# Prop_Fan.net
KiCad netlist of a schematic drawn in EAGLE
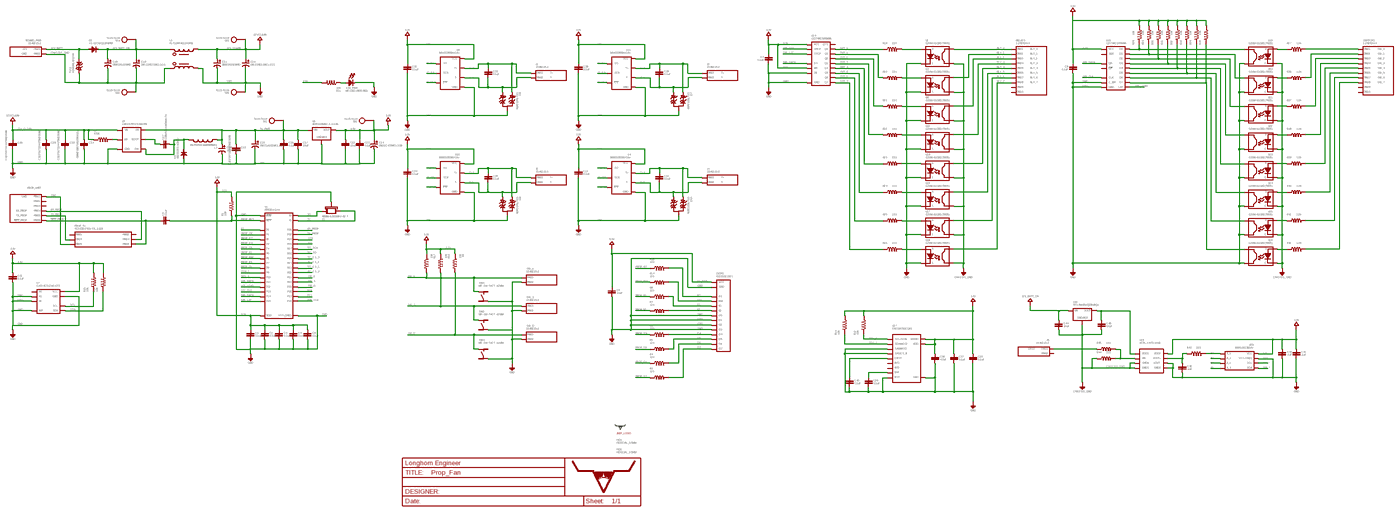
[diagram p0: schematic, sheet 1, overview]
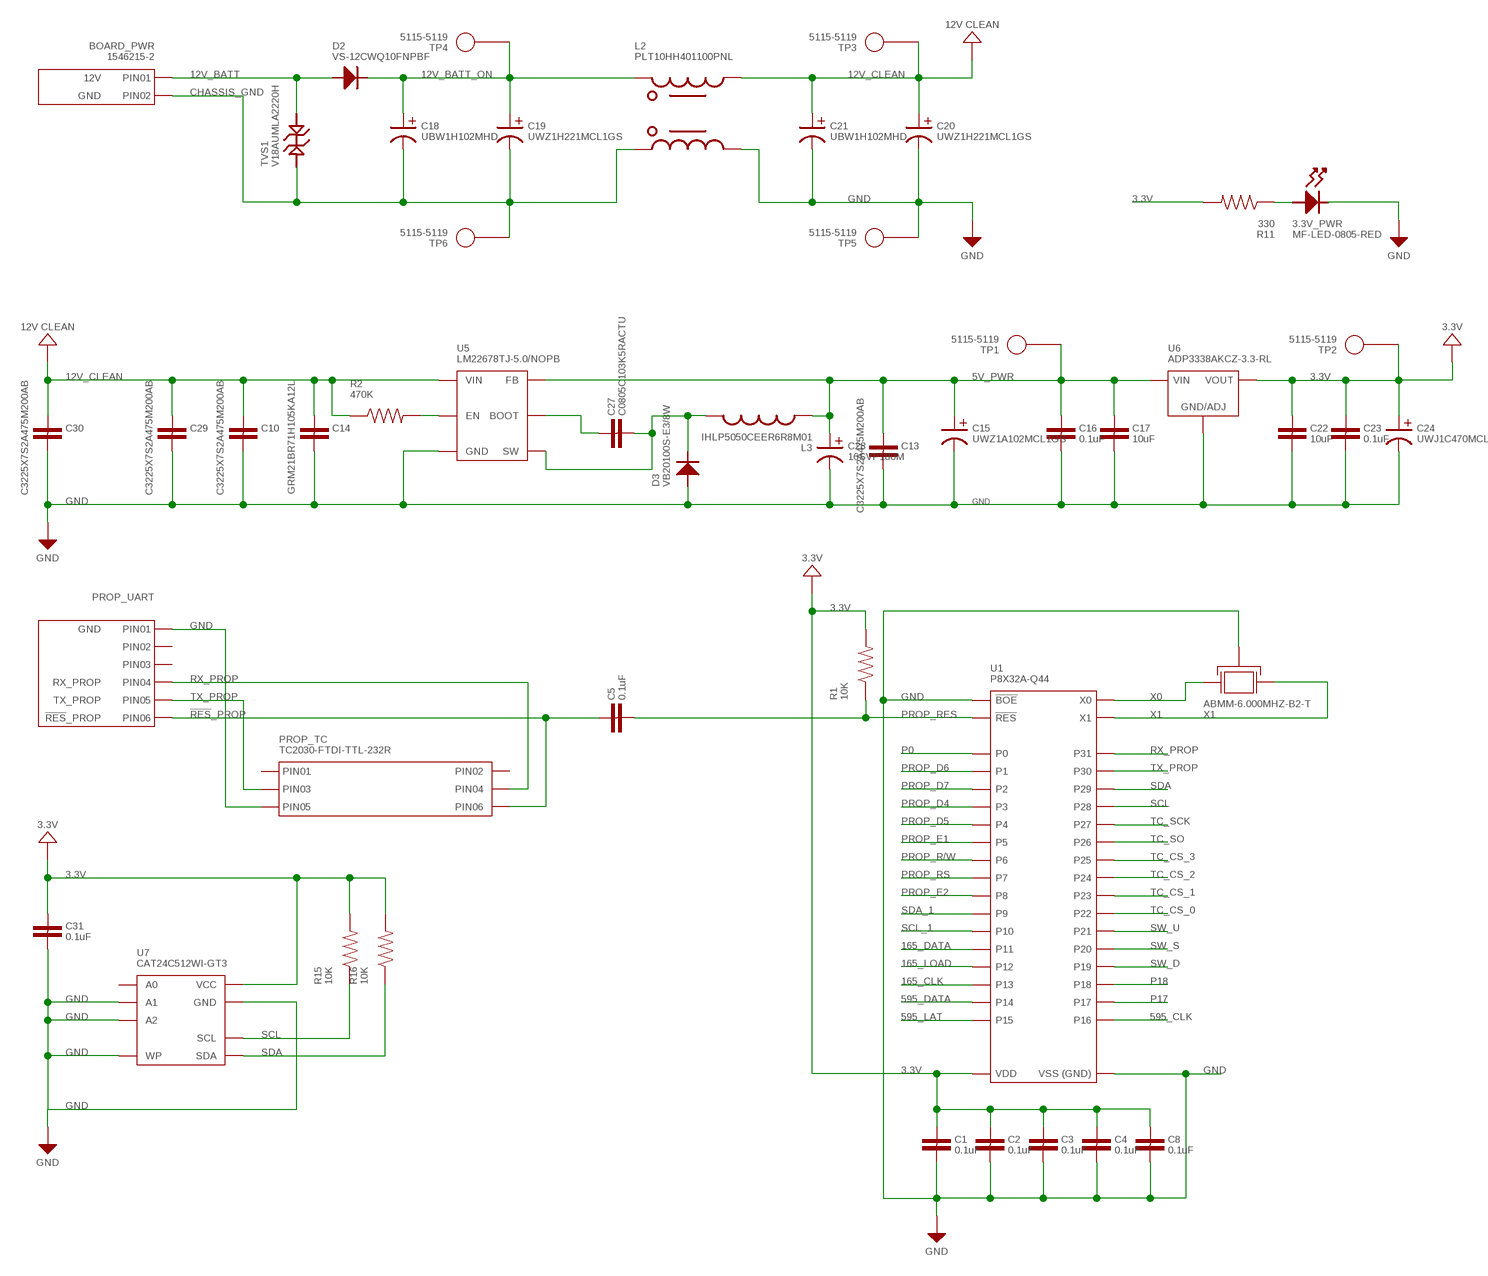
[diagram p1: schematic, sheet 1, part 1 of 4]
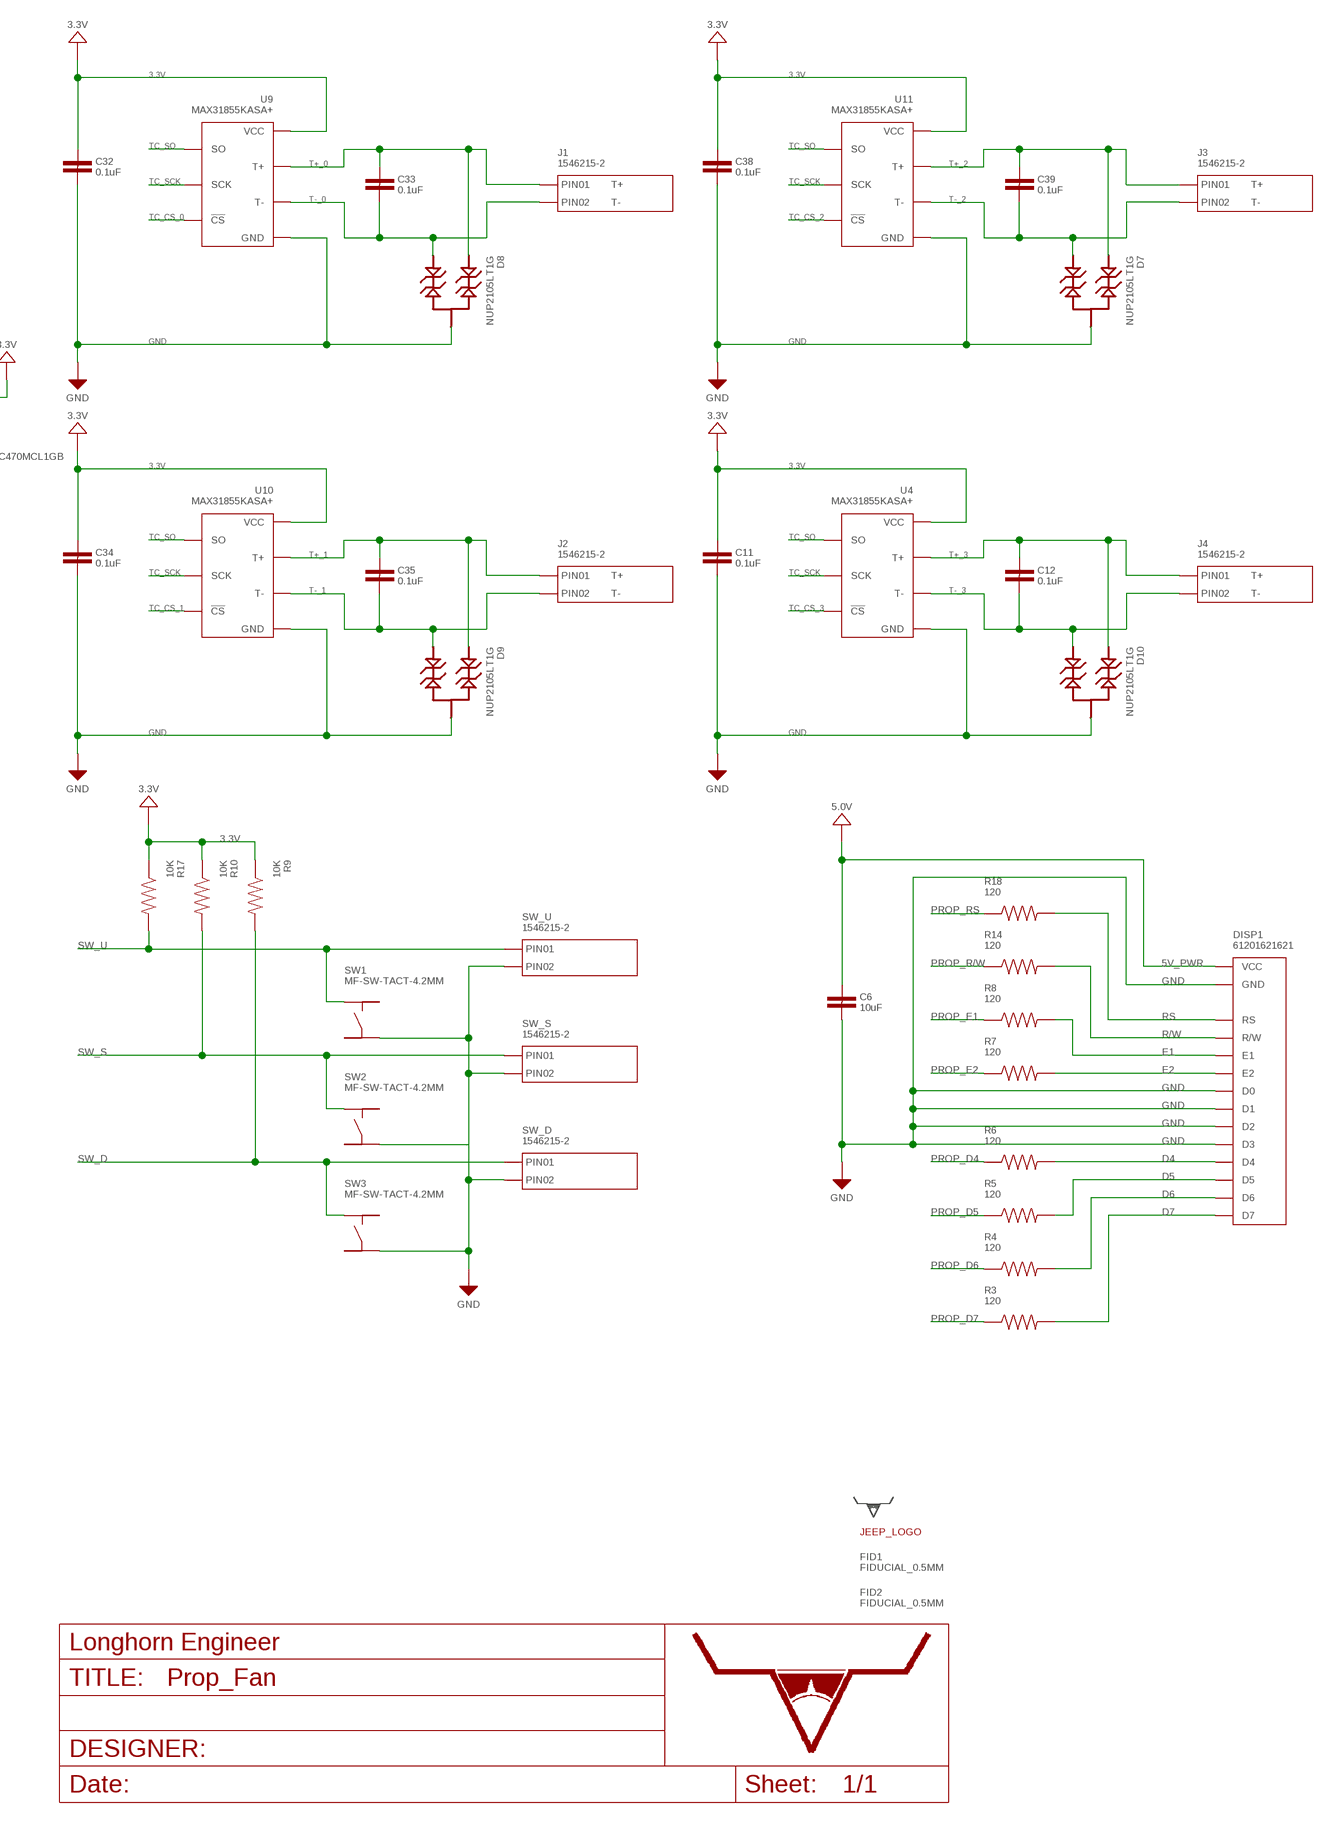
[diagram p2: schematic, sheet 1, part 2 of 4]
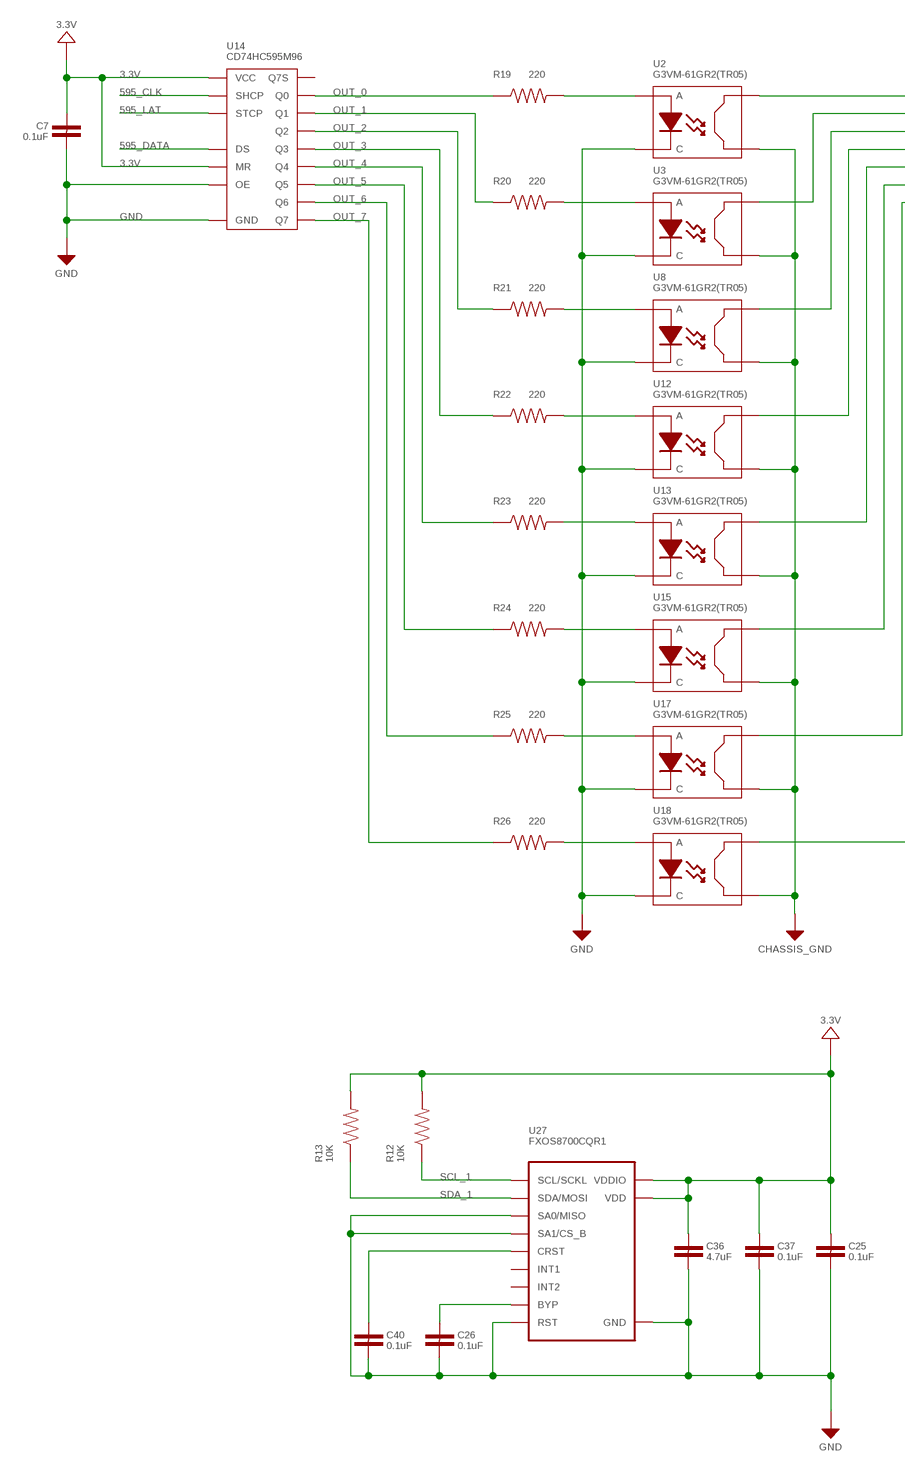
[diagram p3: schematic, sheet 1, part 3 of 4]
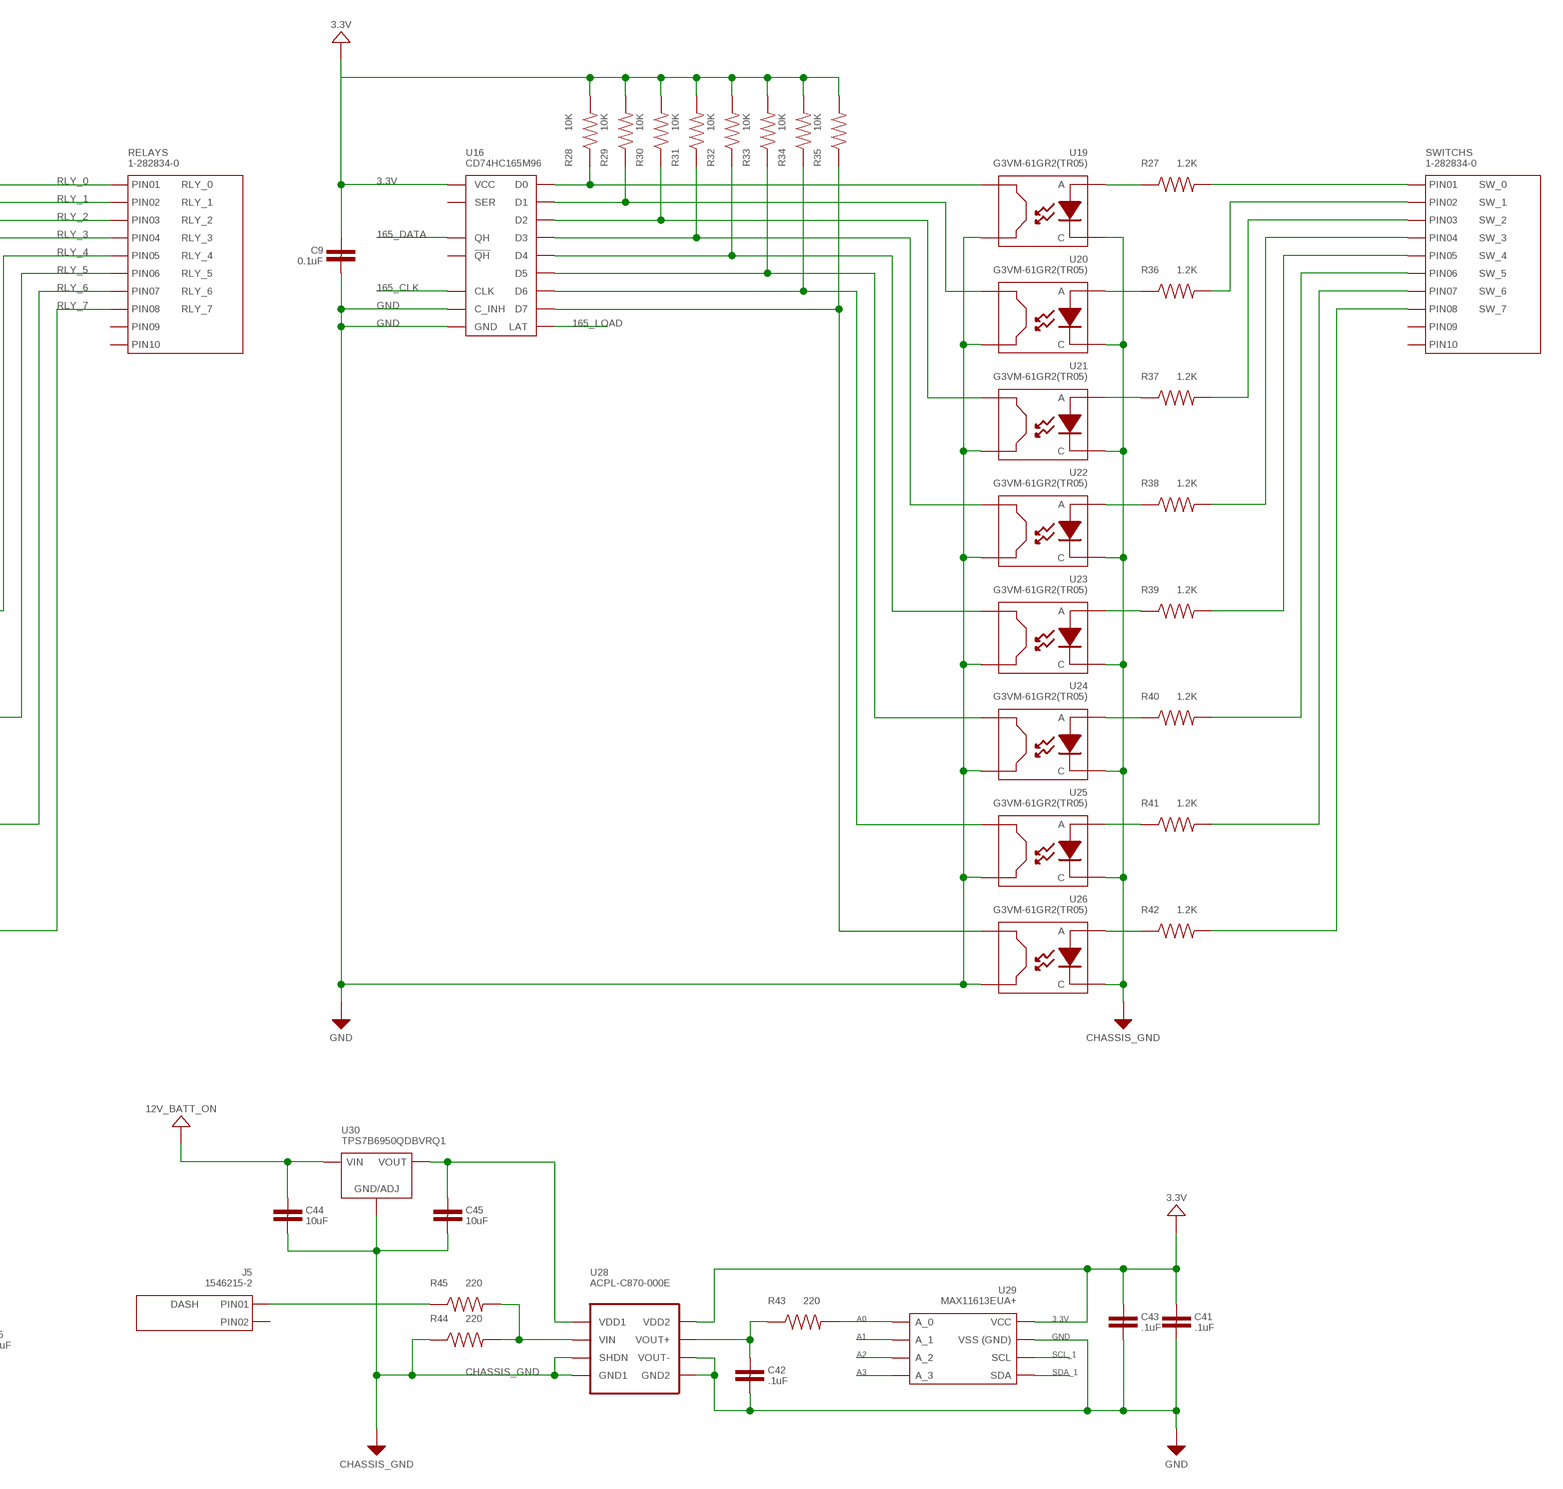
[diagram p4: schematic, sheet 1, part 4 of 4]

(export (version "E")
  (design (tool "Eeschema 10.0.6"))
  (components
    (comp (ref "3.3V_PWR")
      (value "MF-LED-0805-RED")
      (footprint "eagle-import:LED_0805")
      (libsource (lib "eagle-import") (part "LED_SINGLE_0805"))
    )
    (comp (ref "BOARD_PWR")
      (value "1546215-2")
      (footprint "eagle-import:1546215-2")
      (fields (field (name "LABEL01") "12V") (field (name "LABEL02") "GND"))
      (libsource (lib "eagle-import") (part "CON_01X02_1546215-2"))
    )
    (comp (ref "C1")
      (value "0.1uF")
      (footprint "eagle-import:0805")
      (libsource (lib "eagle-import") (part "CAPACITOR_NON_POLAR_0805"))
    )
    (comp (ref "C2")
      (value "0.1uF")
      (footprint "eagle-import:0805")
      (libsource (lib "eagle-import") (part "CAPACITOR_NON_POLAR_0805"))
    )
    (comp (ref "C3")
      (value "0.1uF")
      (footprint "eagle-import:0805")
      (libsource (lib "eagle-import") (part "CAPACITOR_NON_POLAR_0805"))
    )
    (comp (ref "C4")
      (value "0.1uF")
      (footprint "eagle-import:0805")
      (libsource (lib "eagle-import") (part "CAPACITOR_NON_POLAR_0805"))
    )
    (comp (ref "C5")
      (value "0.1uF")
      (footprint "eagle-import:0603")
      (libsource (lib "eagle-import") (part "CAPACITOR_NON_POLAR_0603"))
    )
    (comp (ref "C6")
      (value "10uF")
      (footprint "eagle-import:1210")
      (libsource (lib "eagle-import") (part "CAPACITOR_NON_POLAR_1210"))
    )
    (comp (ref "C7")
      (value "0.1uF")
      (footprint "eagle-import:0805")
      (libsource (lib "eagle-import") (part "CAPACITOR_NON_POLAR_0805"))
    )
    (comp (ref "C8")
      (value "0.1uF")
      (footprint "eagle-import:0805")
      (libsource (lib "eagle-import") (part "CAPACITOR_NON_POLAR_0805"))
    )
    (comp (ref "C9")
      (value "0.1uF")
      (footprint "eagle-import:0805")
      (libsource (lib "eagle-import") (part "CAPACITOR_NON_POLAR_0805"))
    )
    (comp (ref "C10")
      (value "C3225X7S2A475M200AB")
      (footprint "eagle-import:1210")
      (libsource (lib "eagle-import") (part "CAPACITOR_NON_POLAR_1210"))
    )
    (comp (ref "C11")
      (value "0.1uF")
      (footprint "eagle-import:0805")
      (libsource (lib "eagle-import") (part "CAPACITOR_NON_POLAR_0805"))
    )
    (comp (ref "C12")
      (value "0.1uF")
      (footprint "eagle-import:0805")
      (libsource (lib "eagle-import") (part "CAPACITOR_NON_POLAR_0805"))
    )
    (comp (ref "C13")
      (value "C3225X7S2A475M200AB")
      (footprint "eagle-import:1210")
      (libsource (lib "eagle-import") (part "CAPACITOR_NON_POLAR_1210"))
    )
    (comp (ref "C14")
      (value "GRM21BR71H105KA12L")
      (footprint "eagle-import:0805")
      (libsource (lib "eagle-import") (part "CAPACITOR_NON_POLAR_0805"))
    )
    (comp (ref "C15")
      (value "UWZ1A102MCL1GS")
      (footprint "eagle-import:10MM_CAP_SMD")
      (libsource (lib "eagle-import") (part "CAPACITOR_POLARIZED_10MM_SMD"))
    )
    (comp (ref "C16")
      (value "0.1uF")
      (footprint "eagle-import:0805")
      (libsource (lib "eagle-import") (part "CAPACITOR_NON_POLAR_0805"))
    )
    (comp (ref "C17")
      (value "10uF")
      (footprint "eagle-import:1210")
      (libsource (lib "eagle-import") (part "CAPACITOR_NON_POLAR_1210"))
    )
    (comp (ref "C18")
      (value "UBW1H102MHD")
      (footprint "eagle-import:12.5MM_CAP_PTH")
      (libsource (lib "eagle-import") (part "CAPACITOR_POLARIZED_12.5MM_PTH"))
    )
    (comp (ref "C19")
      (value "UWZ1H221MCL1GS")
      (footprint "eagle-import:10MM_CAP_SMD")
      (libsource (lib "eagle-import") (part "CAPACITOR_POLARIZED_10MM_SMD"))
    )
    (comp (ref "C20")
      (value "UWZ1H221MCL1GS")
      (footprint "eagle-import:10MM_CAP_SMD")
      (libsource (lib "eagle-import") (part "CAPACITOR_POLARIZED_10MM_SMD"))
    )
    (comp (ref "C21")
      (value "UBW1H102MHD")
      (footprint "eagle-import:12.5MM_CAP_PTH")
      (libsource (lib "eagle-import") (part "CAPACITOR_POLARIZED_12.5MM_PTH"))
    )
    (comp (ref "C22")
      (value "10uF")
      (footprint "eagle-import:1210")
      (libsource (lib "eagle-import") (part "CAPACITOR_NON_POLAR_1210"))
    )
    (comp (ref "C23")
      (value "0.1uF")
      (footprint "eagle-import:0805")
      (libsource (lib "eagle-import") (part "CAPACITOR_NON_POLAR_0805"))
    )
    (comp (ref "C24")
      (value "UWJ1C470MCL1GB")
      (footprint "eagle-import:6.3MM_CAP_SMD")
      (libsource (lib "eagle-import") (part "CAPACITOR_POLARIZED_6.3MM_SMD"))
    )
    (comp (ref "C25")
      (value "0.1uF")
      (footprint "eagle-import:0805")
      (libsource (lib "eagle-import") (part "CAPACITOR_NON_POLAR_0805"))
    )
    (comp (ref "C26")
      (value "0.1uF")
      (footprint "eagle-import:0805")
      (libsource (lib "eagle-import") (part "CAPACITOR_NON_POLAR_0805"))
    )
    (comp (ref "C27")
      (value "C0805C103K5RACTU")
      (footprint "eagle-import:0805")
      (libsource (lib "eagle-import") (part "CAPACITOR_NON_POLAR_0805"))
    )
    (comp (ref "C28")
      (value "16SVP180M")
      (footprint "eagle-import:8MM_CAP_SMD")
      (libsource (lib "eagle-import") (part "CAPACITOR_POLARIZED_8MM_SMD"))
    )
    (comp (ref "C29")
      (value "C3225X7S2A475M200AB")
      (footprint "eagle-import:1210")
      (libsource (lib "eagle-import") (part "CAPACITOR_NON_POLAR_1210"))
    )
    (comp (ref "C30")
      (value "C3225X7S2A475M200AB")
      (footprint "eagle-import:1210")
      (libsource (lib "eagle-import") (part "CAPACITOR_NON_POLAR_1210"))
    )
    (comp (ref "C31")
      (value "0.1uF")
      (footprint "eagle-import:0805")
      (libsource (lib "eagle-import") (part "CAPACITOR_NON_POLAR_0805"))
    )
    (comp (ref "C32")
      (value "0.1uF")
      (footprint "eagle-import:0805")
      (libsource (lib "eagle-import") (part "CAPACITOR_NON_POLAR_0805"))
    )
    (comp (ref "C33")
      (value "0.1uF")
      (footprint "eagle-import:0805")
      (libsource (lib "eagle-import") (part "CAPACITOR_NON_POLAR_0805"))
    )
    (comp (ref "C34")
      (value "0.1uF")
      (footprint "eagle-import:0805")
      (libsource (lib "eagle-import") (part "CAPACITOR_NON_POLAR_0805"))
    )
    (comp (ref "C35")
      (value "0.1uF")
      (footprint "eagle-import:0805")
      (libsource (lib "eagle-import") (part "CAPACITOR_NON_POLAR_0805"))
    )
    (comp (ref "C36")
      (value "4.7uF")
      (footprint "eagle-import:0805")
      (libsource (lib "eagle-import") (part "CAPACITOR_NON_POLAR_0805"))
    )
    (comp (ref "C37")
      (value "0.1uF")
      (footprint "eagle-import:0805")
      (libsource (lib "eagle-import") (part "CAPACITOR_NON_POLAR_0805"))
    )
    (comp (ref "C38")
      (value "0.1uF")
      (footprint "eagle-import:0805")
      (libsource (lib "eagle-import") (part "CAPACITOR_NON_POLAR_0805"))
    )
    (comp (ref "C39")
      (value "0.1uF")
      (footprint "eagle-import:0805")
      (libsource (lib "eagle-import") (part "CAPACITOR_NON_POLAR_0805"))
    )
    (comp (ref "C40")
      (value "0.1uF")
      (footprint "eagle-import:0805")
      (libsource (lib "eagle-import") (part "CAPACITOR_NON_POLAR_0805"))
    )
    (comp (ref "C41")
      (value ".1uF")
      (footprint "eagle-import:0603")
      (libsource (lib "eagle-import") (part "CAPACITOR_NON_POLAR_0603"))
    )
    (comp (ref "C42")
      (value ".1uF")
      (footprint "eagle-import:0603")
      (libsource (lib "eagle-import") (part "CAPACITOR_NON_POLAR_0603"))
    )
    (comp (ref "C43")
      (value ".1uF")
      (footprint "eagle-import:0603")
      (libsource (lib "eagle-import") (part "CAPACITOR_NON_POLAR_0603"))
    )
    (comp (ref "C44")
      (value "10uF")
      (footprint "eagle-import:1210")
      (libsource (lib "eagle-import") (part "CAPACITOR_NON_POLAR_1210"))
    )
    (comp (ref "C45")
      (value "10uF")
      (footprint "eagle-import:1210")
      (libsource (lib "eagle-import") (part "CAPACITOR_NON_POLAR_1210"))
    )
    (comp (ref "D2")
      (value "VS-12CWQ10FNPBF")
      (footprint "eagle-import:D-PAK(TO-252AA)")
      (libsource (lib "eagle-import") (part "DIODE_D-PAK(TO-252AA)"))
    )
    (comp (ref "D3")
      (value "VB20100S-E3/8W")
      (footprint "eagle-import:D2PAK(TO-263AB)")
      (libsource (lib "eagle-import") (part "DIODE_D2PAK(TO-263AB)"))
    )
    (comp (ref "D7")
      (value "NUP2105LT1G")
      (footprint "eagle-import:SOT-23")
      (libsource (lib "eagle-import") (part "TVS_DIODE_DUALSOT-23"))
    )
    (comp (ref "D8")
      (value "NUP2105LT1G")
      (footprint "eagle-import:SOT-23")
      (libsource (lib "eagle-import") (part "TVS_DIODE_DUALSOT-23"))
    )
    (comp (ref "D9")
      (value "NUP2105LT1G")
      (footprint "eagle-import:SOT-23")
      (libsource (lib "eagle-import") (part "TVS_DIODE_DUALSOT-23"))
    )
    (comp (ref "D10")
      (value "NUP2105LT1G")
      (footprint "eagle-import:SOT-23")
      (libsource (lib "eagle-import") (part "TVS_DIODE_DUALSOT-23"))
    )
    (comp (ref "DISP1")
      (value "61201621621")
      (footprint "eagle-import:CU40045-UW1J")
      (libsource (lib "eagle-import") (part "CU40056-UW1J"))
    )
    (comp (ref "FID1")
      (value "FIDUCIAL_0.5MM")
      (footprint "eagle-import:FIDUCIAL_0.5MM")
      (libsource (lib "eagle-import") (part "FIDUCIAL_0.5MM"))
    )
    (comp (ref "FID2")
      (value "FIDUCIAL_0.5MM")
      (footprint "eagle-import:FIDUCIAL_0.5MM")
      (libsource (lib "eagle-import") (part "FIDUCIAL_0.5MM"))
    )
    (comp (ref "J1")
      (value "1546215-2")
      (footprint "eagle-import:1546215-2")
      (fields (field (name "LABEL01") "T+") (field (name "LABEL02") "T-"))
      (libsource (lib "eagle-import") (part "CON_01X02_1546215-2"))
    )
    (comp (ref "J2")
      (value "1546215-2")
      (footprint "eagle-import:1546215-2")
      (fields (field (name "LABEL01") "T+") (field (name "LABEL02") "T-"))
      (libsource (lib "eagle-import") (part "CON_01X02_1546215-2"))
    )
    (comp (ref "J3")
      (value "1546215-2")
      (footprint "eagle-import:1546215-2")
      (fields (field (name "LABEL01") "T+") (field (name "LABEL02") "T-"))
      (libsource (lib "eagle-import") (part "CON_01X02_1546215-2"))
    )
    (comp (ref "J4")
      (value "1546215-2")
      (footprint "eagle-import:1546215-2")
      (fields (field (name "LABEL01") "T+") (field (name "LABEL02") "T-"))
      (libsource (lib "eagle-import") (part "CON_01X02_1546215-2"))
    )
    (comp (ref "J5")
      (value "1546215-2")
      (footprint "eagle-import:1546215-2")
      (fields (field (name "LABEL01") "DASH"))
      (libsource (lib "eagle-import") (part "CON_01X02_1546215-2"))
    )
    (comp (ref "L2")
      (value "PLT10HH401100PNL")
      (footprint "eagle-import:PLT10H")
      (libsource (lib "eagle-import") (part "COMMON_MODE_INDUCTOR_PLT10H"))
    )
    (comp (ref "L3")
      (value "IHLP5050CEER6R8M01")
      (footprint "eagle-import:IHLP-5050")
      (libsource (lib "eagle-import") (part "INDUCTOR_IHLP-5050"))
    )
    (comp (ref "PROP_TC")
      (value "TC2030-FTDI-TTL-232R")
      (footprint "eagle-import:TC2030")
      (libsource (lib "eagle-import") (part "CON_02X03_TC2030"))
    )
    (comp (ref "PROP_UART")
      (value "CON_01X06_2.54MM_PIN_HEADER")
      (footprint "eagle-import:2.54MM_01X06_PIN_HEADER")
      (fields
        (field (name "LABEL01") "GND")
        (field (name "LABEL04") "RX_PROP")
        (field (name "LABEL05") "TX_PROP")
        (field (name "LABEL06") "!RES!_PROP")
      )
      (libsource (lib "eagle-import") (part "CON_01X06_2.54MM_PIN_HEADER"))
    )
    (comp (ref "R1")
      (value "10K")
      (footprint "eagle-import:0805")
      (libsource (lib "eagle-import") (part "PP_Passives_RESISTOR_0805"))
    )
    (comp (ref "R2")
      (value "470K")
      (footprint "eagle-import:0603")
      (libsource (lib "eagle-import") (part "PP_Passives_RESISTOR_0603"))
    )
    (comp (ref "R3")
      (value "120")
      (footprint "eagle-import:0603")
      (libsource (lib "eagle-import") (part "PP_Passives_RESISTOR_0603"))
    )
    (comp (ref "R4")
      (value "120")
      (footprint "eagle-import:0603")
      (libsource (lib "eagle-import") (part "PP_Passives_RESISTOR_0603"))
    )
    (comp (ref "R5")
      (value "120")
      (footprint "eagle-import:0603")
      (libsource (lib "eagle-import") (part "PP_Passives_RESISTOR_0603"))
    )
    (comp (ref "R6")
      (value "120")
      (footprint "eagle-import:0603")
      (libsource (lib "eagle-import") (part "PP_Passives_RESISTOR_0603"))
    )
    (comp (ref "R7")
      (value "120")
      (footprint "eagle-import:0603")
      (libsource (lib "eagle-import") (part "PP_Passives_RESISTOR_0603"))
    )
    (comp (ref "R8")
      (value "120")
      (footprint "eagle-import:0603")
      (libsource (lib "eagle-import") (part "PP_Passives_RESISTOR_0603"))
    )
    (comp (ref "R9")
      (value "10K")
      (footprint "eagle-import:0805")
      (libsource (lib "eagle-import") (part "PP_Passives_RESISTOR_0805"))
    )
    (comp (ref "R10")
      (value "10K")
      (footprint "eagle-import:0805")
      (libsource (lib "eagle-import") (part "PP_Passives_RESISTOR_0805"))
    )
    (comp (ref "R11")
      (value "330")
      (footprint "eagle-import:0603")
      (libsource (lib "eagle-import") (part "PP_Passives_RESISTOR_0603"))
    )
    (comp (ref "R12")
      (value "10K")
      (footprint "eagle-import:0603")
      (libsource (lib "eagle-import") (part "PP_Passives_RESISTOR_0603"))
    )
    (comp (ref "R13")
      (value "10K")
      (footprint "eagle-import:0603")
      (libsource (lib "eagle-import") (part "PP_Passives_RESISTOR_0603"))
    )
    (comp (ref "R14")
      (value "120")
      (footprint "eagle-import:0603")
      (libsource (lib "eagle-import") (part "PP_Passives_RESISTOR_0603"))
    )
    (comp (ref "R15")
      (value "10K")
      (footprint "eagle-import:0805")
      (libsource (lib "eagle-import") (part "PP_Passives_RESISTOR_0805"))
    )
    (comp (ref "R16")
      (value "10K")
      (footprint "eagle-import:0805")
      (libsource (lib "eagle-import") (part "PP_Passives_RESISTOR_0805"))
    )
    (comp (ref "R17")
      (value "10K")
      (footprint "eagle-import:0805")
      (libsource (lib "eagle-import") (part "PP_Passives_RESISTOR_0805"))
    )
    (comp (ref "R18")
      (value "120")
      (footprint "eagle-import:0603")
      (libsource (lib "eagle-import") (part "PP_Passives_RESISTOR_0603"))
    )
    (comp (ref "R19")
      (value "220")
      (footprint "eagle-import:R0603")
      (libsource (lib "eagle-import") (part "RESISTOR_0603"))
    )
    (comp (ref "R20")
      (value "220")
      (footprint "eagle-import:R0603")
      (libsource (lib "eagle-import") (part "RESISTOR_0603"))
    )
    (comp (ref "R21")
      (value "220")
      (footprint "eagle-import:R0603")
      (libsource (lib "eagle-import") (part "RESISTOR_0603"))
    )
    (comp (ref "R22")
      (value "220")
      (footprint "eagle-import:R0603")
      (libsource (lib "eagle-import") (part "RESISTOR_0603"))
    )
    (comp (ref "R23")
      (value "220")
      (footprint "eagle-import:R0603")
      (libsource (lib "eagle-import") (part "RESISTOR_0603"))
    )
    (comp (ref "R24")
      (value "220")
      (footprint "eagle-import:R0603")
      (libsource (lib "eagle-import") (part "RESISTOR_0603"))
    )
    (comp (ref "R25")
      (value "220")
      (footprint "eagle-import:R0603")
      (libsource (lib "eagle-import") (part "RESISTOR_0603"))
    )
    (comp (ref "R26")
      (value "220")
      (footprint "eagle-import:R0603")
      (libsource (lib "eagle-import") (part "RESISTOR_0603"))
    )
    (comp (ref "R27")
      (value "1.2K")
      (footprint "eagle-import:R0603")
      (libsource (lib "eagle-import") (part "RESISTOR_0603"))
    )
    (comp (ref "R28")
      (value "10K")
      (footprint "eagle-import:R0603")
      (libsource (lib "eagle-import") (part "RESISTOR_0603"))
    )
    (comp (ref "R29")
      (value "10K")
      (footprint "eagle-import:R0603")
      (libsource (lib "eagle-import") (part "RESISTOR_0603"))
    )
    (comp (ref "R30")
      (value "10K")
      (footprint "eagle-import:R0603")
      (libsource (lib "eagle-import") (part "RESISTOR_0603"))
    )
    (comp (ref "R31")
      (value "10K")
      (footprint "eagle-import:R0603")
      (libsource (lib "eagle-import") (part "RESISTOR_0603"))
    )
    (comp (ref "R32")
      (value "10K")
      (footprint "eagle-import:R0603")
      (libsource (lib "eagle-import") (part "RESISTOR_0603"))
    )
    (comp (ref "R33")
      (value "10K")
      (footprint "eagle-import:R0603")
      (libsource (lib "eagle-import") (part "RESISTOR_0603"))
    )
    (comp (ref "R34")
      (value "10K")
      (footprint "eagle-import:R0603")
      (libsource (lib "eagle-import") (part "RESISTOR_0603"))
    )
    (comp (ref "R35")
      (value "10K")
      (footprint "eagle-import:R0603")
      (libsource (lib "eagle-import") (part "RESISTOR_0603"))
    )
    (comp (ref "R36")
      (value "1.2K")
      (footprint "eagle-import:R0603")
      (libsource (lib "eagle-import") (part "RESISTOR_0603"))
    )
    (comp (ref "R37")
      (value "1.2K")
      (footprint "eagle-import:R0603")
      (libsource (lib "eagle-import") (part "RESISTOR_0603"))
    )
    (comp (ref "R38")
      (value "1.2K")
      (footprint "eagle-import:R0603")
      (libsource (lib "eagle-import") (part "RESISTOR_0603"))
    )
    (comp (ref "R39")
      (value "1.2K")
      (footprint "eagle-import:R0603")
      (libsource (lib "eagle-import") (part "RESISTOR_0603"))
    )
    (comp (ref "R40")
      (value "1.2K")
      (footprint "eagle-import:R0603")
      (libsource (lib "eagle-import") (part "RESISTOR_0603"))
    )
    (comp (ref "R41")
      (value "1.2K")
      (footprint "eagle-import:R0603")
      (libsource (lib "eagle-import") (part "RESISTOR_0603"))
    )
    (comp (ref "R42")
      (value "1.2K")
      (footprint "eagle-import:R0603")
      (libsource (lib "eagle-import") (part "RESISTOR_0603"))
    )
    (comp (ref "R43")
      (value "220")
      (footprint "eagle-import:R0603")
      (libsource (lib "eagle-import") (part "RESISTOR_0603"))
    )
    (comp (ref "R44")
      (value "220")
      (footprint "eagle-import:R0603")
      (libsource (lib "eagle-import") (part "RESISTOR_0603"))
    )
    (comp (ref "R45")
      (value "220")
      (footprint "eagle-import:R0603")
      (libsource (lib "eagle-import") (part "RESISTOR_0603"))
    )
    (comp (ref "RELAYS")
      (value "1-282834-0")
      (footprint "eagle-import:1-282834-0")
      (fields
        (field (name "LABEL01") "RLY_0")
        (field (name "LABEL02") "RLY_1")
        (field (name "LABEL03") "RLY_2")
        (field (name "LABEL04") "RLY_3")
        (field (name "LABEL05") "RLY_4")
        (field (name "LABEL06") "RLY_5")
        (field (name "LABEL07") "RLY_6")
        (field (name "LABEL08") "RLY_7")
      )
      (libsource (lib "eagle-import") (part "CON_01X10_1-282834-0"))
    )
    (comp (ref "SW1")
      (value "MF-SW-TACT-4.2MM")
      (footprint "eagle-import:TACT4.2MM")
      (libsource (lib "eagle-import") (part "TACT_4.2MM"))
    )
    (comp (ref "SW2")
      (value "MF-SW-TACT-4.2MM")
      (footprint "eagle-import:TACT4.2MM")
      (libsource (lib "eagle-import") (part "TACT_4.2MM"))
    )
    (comp (ref "SW3")
      (value "MF-SW-TACT-4.2MM")
      (footprint "eagle-import:TACT4.2MM")
      (libsource (lib "eagle-import") (part "TACT_4.2MM"))
    )
    (comp (ref "SWITCHS")
      (value "1-282834-0")
      (footprint "eagle-import:1-282834-0")
      (fields
        (field (name "LABEL01") "SW_0")
        (field (name "LABEL02") "SW_1")
        (field (name "LABEL03") "SW_2")
        (field (name "LABEL04") "SW_3")
        (field (name "LABEL05") "SW_4")
        (field (name "LABEL06") "SW_5")
        (field (name "LABEL07") "SW_6")
        (field (name "LABEL08") "SW_7")
      )
      (libsource (lib "eagle-import") (part "CON_01X10_1-282834-0"))
    )
    (comp (ref "SW_D")
      (value "1546215-2")
      (footprint "eagle-import:1546215-2")
      (libsource (lib "eagle-import") (part "CON_01X02_1546215-2"))
    )
    (comp (ref "SW_S")
      (value "1546215-2")
      (footprint "eagle-import:1546215-2")
      (libsource (lib "eagle-import") (part "CON_01X02_1546215-2"))
    )
    (comp (ref "SW_U")
      (value "1546215-2")
      (footprint "eagle-import:1546215-2")
      (libsource (lib "eagle-import") (part "CON_01X02_1546215-2"))
    )
    (comp (ref "TP1")
      (value "5115-5119")
      (footprint "eagle-import:KEYSTONE_5115-5119")
      (libsource (lib "eagle-import") (part "TEST_POINT_SINGLE_KEYSTONE_5115-5119"))
    )
    (comp (ref "TP2")
      (value "5115-5119")
      (footprint "eagle-import:KEYSTONE_5115-5119")
      (libsource (lib "eagle-import") (part "TEST_POINT_SINGLE_KEYSTONE_5115-5119"))
    )
    (comp (ref "TP3")
      (value "5115-5119")
      (footprint "eagle-import:KEYSTONE_5115-5119")
      (libsource (lib "eagle-import") (part "TEST_POINT_SINGLE_KEYSTONE_5115-5119"))
    )
    (comp (ref "TP4")
      (value "5115-5119")
      (footprint "eagle-import:KEYSTONE_5115-5119")
      (libsource (lib "eagle-import") (part "TEST_POINT_SINGLE_KEYSTONE_5115-5119"))
    )
    (comp (ref "TP5")
      (value "5115-5119")
      (footprint "eagle-import:KEYSTONE_5115-5119")
      (libsource (lib "eagle-import") (part "TEST_POINT_SINGLE_KEYSTONE_5115-5119"))
    )
    (comp (ref "TP6")
      (value "5115-5119")
      (footprint "eagle-import:KEYSTONE_5115-5119")
      (libsource (lib "eagle-import") (part "TEST_POINT_SINGLE_KEYSTONE_5115-5119"))
    )
    (comp (ref "TVS1")
      (value "V18AUMLA2220H")
      (footprint "eagle-import:2220")
      (libsource (lib "eagle-import") (part "TVS_DIODE_2220"))
    )
    (comp (ref "U$1")
      (value "LHE_FRAME")
      (footprint "eagle-import:LHE_FRAME")
      (fields (field (name "DNAME") "Parker Dillmann") (field (name "REVNUM") "REV: 1"))
      (libsource (lib "eagle-import") (part "LHE_FRAME"))
    )
    (comp (ref "U$35")
      (value "JEEP_LOGO_SILK_MEDIUM")
      (footprint "eagle-import:JEEP_SILK_MEDIUM")
      (libsource (lib "eagle-import") (part "JEEP_LOGO_SILK_MEDIUM"))
    )
    (comp (ref "U$42")
      (value "LHE_LOGOLHE_LOGO")
      (footprint "eagle-import:LHE_LOGO")
      (libsource (lib "eagle-import") (part "LHE_LOGOLHE_LOGO"))
    )
    (comp (ref "U1")
      (value "P8X32A-Q44")
      (footprint "eagle-import:LQFP44")
      (libsource (lib "eagle-import") (part "P8X32A-Q44"))
    )
    (comp (ref "U2")
      (value "G3VM-61GR2(TR05)")
      (footprint "eagle-import:G3VM-61GR2")
      (libsource (lib "eagle-import") (part "G3VM-61GR2"))
    )
    (comp (ref "U3")
      (value "G3VM-61GR2(TR05)")
      (footprint "eagle-import:G3VM-61GR2")
      (libsource (lib "eagle-import") (part "G3VM-61GR2"))
    )
    (comp (ref "U4")
      (value "MAX31855KASA+")
      (footprint "eagle-import:MAX31855_SO-8")
      (libsource (lib "eagle-import") (part "MAX31855"))
    )
    (comp (ref "U5")
      (value "LM22678TJ-5.0/NOPB")
      (footprint "eagle-import:LM22678_TO-263-EP-7")
      (libsource (lib "eagle-import") (part "LM22678"))
    )
    (comp (ref "U6")
      (value "ADP3338AKCZ-3.3-RL")
      (footprint "eagle-import:ADP3338_SOT-223-3")
      (libsource (lib "eagle-import") (part "LINEAR_VOTLAGE_REGULATORS_ADP3338"))
    )
    (comp (ref "U7")
      (value "CAT24C512WI-GT3")
      (footprint "eagle-import:SOIC-8_W")
      (libsource (lib "eagle-import") (part "EEPROM_I2CSOIC-8_W"))
    )
    (comp (ref "U8")
      (value "G3VM-61GR2(TR05)")
      (footprint "eagle-import:G3VM-61GR2")
      (libsource (lib "eagle-import") (part "G3VM-61GR2"))
    )
    (comp (ref "U9")
      (value "MAX31855KASA+")
      (footprint "eagle-import:MAX31855_SO-8")
      (libsource (lib "eagle-import") (part "MAX31855"))
    )
    (comp (ref "U10")
      (value "MAX31855KASA+")
      (footprint "eagle-import:MAX31855_SO-8")
      (libsource (lib "eagle-import") (part "MAX31855"))
    )
    (comp (ref "U11")
      (value "MAX31855KASA+")
      (footprint "eagle-import:MAX31855_SO-8")
      (libsource (lib "eagle-import") (part "MAX31855"))
    )
    (comp (ref "U12")
      (value "G3VM-61GR2(TR05)")
      (footprint "eagle-import:G3VM-61GR2")
      (libsource (lib "eagle-import") (part "G3VM-61GR2"))
    )
    (comp (ref "U13")
      (value "G3VM-61GR2(TR05)")
      (footprint "eagle-import:G3VM-61GR2")
      (libsource (lib "eagle-import") (part "G3VM-61GR2"))
    )
    (comp (ref "U14")
      (value "CD74HC595M96")
      (footprint "eagle-import:CD74HC595_SOIC-16")
      (libsource (lib "eagle-import") (part "CD74HC595M96"))
    )
    (comp (ref "U15")
      (value "G3VM-61GR2(TR05)")
      (footprint "eagle-import:G3VM-61GR2")
      (libsource (lib "eagle-import") (part "G3VM-61GR2"))
    )
    (comp (ref "U16")
      (value "CD74HC165M96")
      (footprint "eagle-import:CD74HC165_SOIC-16")
      (libsource (lib "eagle-import") (part "CD74HC165M96"))
    )
    (comp (ref "U17")
      (value "G3VM-61GR2(TR05)")
      (footprint "eagle-import:G3VM-61GR2")
      (libsource (lib "eagle-import") (part "G3VM-61GR2"))
    )
    (comp (ref "U18")
      (value "G3VM-61GR2(TR05)")
      (footprint "eagle-import:G3VM-61GR2")
      (libsource (lib "eagle-import") (part "G3VM-61GR2"))
    )
    (comp (ref "U19")
      (value "G3VM-61GR2(TR05)")
      (footprint "eagle-import:G3VM-61GR2")
      (libsource (lib "eagle-import") (part "G3VM-61GR2"))
    )
    (comp (ref "U20")
      (value "G3VM-61GR2(TR05)")
      (footprint "eagle-import:G3VM-61GR2")
      (libsource (lib "eagle-import") (part "G3VM-61GR2"))
    )
    (comp (ref "U21")
      (value "G3VM-61GR2(TR05)")
      (footprint "eagle-import:G3VM-61GR2")
      (libsource (lib "eagle-import") (part "G3VM-61GR2"))
    )
    (comp (ref "U22")
      (value "G3VM-61GR2(TR05)")
      (footprint "eagle-import:G3VM-61GR2")
      (libsource (lib "eagle-import") (part "G3VM-61GR2"))
    )
    (comp (ref "U23")
      (value "G3VM-61GR2(TR05)")
      (footprint "eagle-import:G3VM-61GR2")
      (libsource (lib "eagle-import") (part "G3VM-61GR2"))
    )
    (comp (ref "U24")
      (value "G3VM-61GR2(TR05)")
      (footprint "eagle-import:G3VM-61GR2")
      (libsource (lib "eagle-import") (part "G3VM-61GR2"))
    )
    (comp (ref "U25")
      (value "G3VM-61GR2(TR05)")
      (footprint "eagle-import:G3VM-61GR2")
      (libsource (lib "eagle-import") (part "G3VM-61GR2"))
    )
    (comp (ref "U26")
      (value "G3VM-61GR2(TR05)")
      (footprint "eagle-import:G3VM-61GR2")
      (libsource (lib "eagle-import") (part "G3VM-61GR2"))
    )
    (comp (ref "U27")
      (value "FXOS8700CQR1")
      (footprint "eagle-import:FXOS8700CQR1")
      (libsource (lib "eagle-import") (part "FXOS8700CQR1"))
    )
    (comp (ref "U28")
      (value "ACPL-C870-000E")
      (footprint "eagle-import:ACPL-C87_SSO-8")
      (libsource (lib "eagle-import") (part "ACPL-C87X"))
    )
    (comp (ref "U29")
      (value "MAX11613EUA+")
      (footprint "eagle-import:MAX11613_UMAX-8")
      (libsource (lib "eagle-import") (part "MAX11613EUA+"))
    )
    (comp (ref "U30")
      (value "TPS7B6950QDBVRQ1")
      (footprint "eagle-import:SOT-23-5")
      (libsource (lib "eagle-import") (part "TPS7B69"))
    )
    (comp (ref "X1")
      (value "ABMM-6.000MHZ-B2-T")
      (footprint "eagle-import:7MMX5MM")
      (libsource (lib "eagle-import") (part "XTL_7MMX5MM"))
    )
  )
  (nets
    (net (code "1") (name "/12V_BATT") (class "Default")
      (node (ref "BOARD_PWR") (pin "P$1") (pinfunction "PIN1_P$1") (pintype "bidirectional"))
      (node (ref "D2") (pin "1") (pinfunction "ANODE_1") (pintype "bidirectional"))
      (node (ref "D2") (pin "3") (pinfunction "ANODE_3") (pintype "bidirectional"))
      (node (ref "TVS1") (pin "P$2") (pinfunction "P$2_P$2") (pintype "bidirectional"))
    )
    (net (code "2") (name "/165_CLK") (class "Default")
      (node (ref "U1") (pin "14") (pinfunction "P13_14") (pintype "bidirectional"))
      (node (ref "U16") (pin "2") (pinfunction "CLK_2") (pintype "bidirectional"))
    )
    (net (code "3") (name "/165_DATA") (class "Default")
      (node (ref "U1") (pin "12") (pinfunction "P11_12") (pintype "bidirectional"))
      (node (ref "U16") (pin "9") (pinfunction "QH_9") (pintype "bidirectional"))
    )
    (net (code "4") (name "/165_LOAD") (class "Default")
      (node (ref "U1") (pin "13") (pinfunction "P12_13") (pintype "bidirectional"))
      (node (ref "U16") (pin "1") (pinfunction "LAT_1") (pintype "bidirectional"))
    )
    (net (code "5") (name "/595_CLK") (class "Default")
      (node (ref "U1") (pin "19") (pinfunction "P16_19") (pintype "bidirectional"))
      (node (ref "U14") (pin "11") (pinfunction "SHCP_11") (pintype "bidirectional"))
    )
    (net (code "6") (name "/595_DATA") (class "Default")
      (node (ref "U1") (pin "15") (pinfunction "P14_15") (pintype "bidirectional"))
      (node (ref "U14") (pin "14") (pinfunction "DS_14") (pintype "bidirectional"))
    )
    (net (code "7") (name "/595_LAT") (class "Default")
      (node (ref "U1") (pin "16") (pinfunction "P15_16") (pintype "bidirectional"))
      (node (ref "U14") (pin "12") (pinfunction "STCP_12") (pintype "bidirectional"))
    )
    (net (code "8") (name "/A0") (class "Default")
      (node (ref "R43") (pin "P$2") (pinfunction "P$2_P$2") (pintype "passive"))
      (node (ref "U29") (pin "P$1") (pinfunction "A_0_P$1") (pintype "bidirectional"))
    )
    (net (code "9") (name "/A1") (class "Default")
      (node (ref "U29") (pin "P$2") (pinfunction "A_1_P$2") (pintype "bidirectional"))
    )
    (net (code "10") (name "/A2") (class "Default")
      (node (ref "U29") (pin "P$3") (pinfunction "A_2_P$3") (pintype "bidirectional"))
    )
    (net (code "11") (name "/A3") (class "Default")
      (node (ref "U29") (pin "P$4") (pinfunction "A_3_P$4") (pintype "bidirectional"))
    )
    (net (code "12") (name "/D4") (class "Default")
      (node (ref "DISP1") (pin "P$3") (pinfunction "D4_P$3") (pintype "bidirectional"))
      (node (ref "R6") (pin "2") (pinfunction "2_2") (pintype "passive"))
    )
    (net (code "13") (name "/D5") (class "Default")
      (node (ref "DISP1") (pin "P$4") (pinfunction "D5_P$4") (pintype "bidirectional"))
      (node (ref "R5") (pin "2") (pinfunction "2_2") (pintype "passive"))
    )
    (net (code "14") (name "/D6") (class "Default")
      (node (ref "DISP1") (pin "P$1") (pinfunction "D6_P$1") (pintype "bidirectional"))
      (node (ref "R4") (pin "2") (pinfunction "2_2") (pintype "passive"))
    )
    (net (code "15") (name "/D7") (class "Default")
      (node (ref "DISP1") (pin "P$2") (pinfunction "D7_P$2") (pintype "bidirectional"))
      (node (ref "R3") (pin "2") (pinfunction "2_2") (pintype "passive"))
    )
    (net (code "16") (name "/E1") (class "Default")
      (node (ref "DISP1") (pin "P$10") (pinfunction "E1_P$10") (pintype "bidirectional"))
      (node (ref "R8") (pin "2") (pinfunction "2_2") (pintype "passive"))
    )
    (net (code "17") (name "/E2") (class "Default")
      (node (ref "DISP1") (pin "P$16") (pinfunction "E2_P$16") (pintype "bidirectional"))
      (node (ref "R7") (pin "2") (pinfunction "2_2") (pintype "passive"))
    )
    (net (code "18") (name "/OUT_0") (class "Default")
      (node (ref "R19") (pin "P$1") (pinfunction "P$1_P$1") (pintype "passive"))
      (node (ref "U14") (pin "15") (pinfunction "Q0_15") (pintype "bidirectional"))
    )
    (net (code "19") (name "/OUT_1") (class "Default")
      (node (ref "R20") (pin "P$1") (pinfunction "P$1_P$1") (pintype "passive"))
      (node (ref "U14") (pin "1") (pinfunction "Q1_1") (pintype "bidirectional"))
    )
    (net (code "20") (name "/OUT_2") (class "Default")
      (node (ref "R21") (pin "P$1") (pinfunction "P$1_P$1") (pintype "passive"))
      (node (ref "U14") (pin "2") (pinfunction "Q2_2") (pintype "bidirectional"))
    )
    (net (code "21") (name "/OUT_3") (class "Default")
      (node (ref "R22") (pin "P$1") (pinfunction "P$1_P$1") (pintype "passive"))
      (node (ref "U14") (pin "3") (pinfunction "Q3_3") (pintype "bidirectional"))
    )
    (net (code "22") (name "/OUT_4") (class "Default")
      (node (ref "R23") (pin "P$1") (pinfunction "P$1_P$1") (pintype "passive"))
      (node (ref "U14") (pin "4") (pinfunction "Q4_4") (pintype "bidirectional"))
    )
    (net (code "23") (name "/OUT_5") (class "Default")
      (node (ref "R24") (pin "P$1") (pinfunction "P$1_P$1") (pintype "passive"))
      (node (ref "U14") (pin "5") (pinfunction "Q5_5") (pintype "bidirectional"))
    )
    (net (code "24") (name "/OUT_6") (class "Default")
      (node (ref "R25") (pin "P$1") (pinfunction "P$1_P$1") (pintype "passive"))
      (node (ref "U14") (pin "6") (pinfunction "Q6_6") (pintype "bidirectional"))
    )
    (net (code "25") (name "/OUT_7") (class "Default")
      (node (ref "R26") (pin "P$1") (pinfunction "P$1_P$1") (pintype "passive"))
      (node (ref "U14") (pin "7") (pinfunction "Q7_7") (pintype "bidirectional"))
    )
    (net (code "26") (name "/P0") (class "Default")
      (node (ref "U1") (pin "41") (pinfunction "P0_41") (pintype "bidirectional"))
    )
    (net (code "27") (name "/P17") (class "Default")
      (node (ref "U1") (pin "20") (pinfunction "P17_20") (pintype "bidirectional"))
    )
    (net (code "28") (name "/P18") (class "Default")
      (node (ref "U1") (pin "21") (pinfunction "P18_21") (pintype "bidirectional"))
    )
    (net (code "29") (name "/PROP_D4") (class "Default")
      (node (ref "R6") (pin "1") (pinfunction "1_1") (pintype "passive"))
      (node (ref "U1") (pin "44") (pinfunction "P3_44") (pintype "bidirectional"))
    )
    (net (code "30") (name "/PROP_D5") (class "Default")
      (node (ref "R5") (pin "1") (pinfunction "1_1") (pintype "passive"))
      (node (ref "U1") (pin "1") (pinfunction "P4_1") (pintype "bidirectional"))
    )
    (net (code "31") (name "/PROP_D6") (class "Default")
      (node (ref "R4") (pin "1") (pinfunction "1_1") (pintype "passive"))
      (node (ref "U1") (pin "42") (pinfunction "P1_42") (pintype "bidirectional"))
    )
    (net (code "32") (name "/PROP_D7") (class "Default")
      (node (ref "R3") (pin "1") (pinfunction "1_1") (pintype "passive"))
      (node (ref "U1") (pin "43") (pinfunction "P2_43") (pintype "bidirectional"))
    )
    (net (code "33") (name "/PROP_E1") (class "Default")
      (node (ref "R8") (pin "1") (pinfunction "1_1") (pintype "passive"))
      (node (ref "U1") (pin "2") (pinfunction "P5_2") (pintype "bidirectional"))
    )
    (net (code "34") (name "/PROP_E2") (class "Default")
      (node (ref "R7") (pin "1") (pinfunction "1_1") (pintype "passive"))
      (node (ref "U1") (pin "9") (pinfunction "P8_9") (pintype "bidirectional"))
    )
    (net (code "35") (name "/PROP_RES") (class "Default")
      (node (ref "C5") (pin "2") (pinfunction "2_2") (pintype "passive"))
      (node (ref "R1") (pin "1") (pinfunction "1_1") (pintype "passive"))
      (node (ref "U1") (pin "7") (pinfunction "RES'_7") (pintype "bidirectional"))
    )
    (net (code "36") (name "/PROP_RS") (class "Default")
      (node (ref "R18") (pin "1") (pinfunction "1_1") (pintype "passive"))
      (node (ref "U1") (pin "4") (pinfunction "P7_4") (pintype "bidirectional"))
    )
    (net (code "37") (name "/PROP_R{slash}W") (class "Default")
      (node (ref "R14") (pin "1") (pinfunction "1_1") (pintype "passive"))
      (node (ref "U1") (pin "3") (pinfunction "P6_3") (pintype "bidirectional"))
    )
    (net (code "38") (name "/RLY_0") (class "Default")
      (node (ref "RELAYS") (pin "P$1") (pinfunction "1_P$1") (pintype "bidirectional"))
      (node (ref "U2") (pin "P$4") (pinfunction "4_P$4") (pintype "bidirectional"))
    )
    (net (code "39") (name "/RLY_1") (class "Default")
      (node (ref "RELAYS") (pin "P$2") (pinfunction "2_P$2") (pintype "bidirectional"))
      (node (ref "U3") (pin "P$4") (pinfunction "4_P$4") (pintype "bidirectional"))
    )
    (net (code "40") (name "/RLY_2") (class "Default")
      (node (ref "RELAYS") (pin "P$3") (pinfunction "3_P$3") (pintype "bidirectional"))
      (node (ref "U8") (pin "P$4") (pinfunction "4_P$4") (pintype "bidirectional"))
    )
    (net (code "41") (name "/RLY_3") (class "Default")
      (node (ref "RELAYS") (pin "P$4") (pinfunction "4_P$4") (pintype "bidirectional"))
      (node (ref "U12") (pin "P$4") (pinfunction "4_P$4") (pintype "bidirectional"))
    )
    (net (code "42") (name "/RLY_4") (class "Default")
      (node (ref "RELAYS") (pin "P$5") (pinfunction "5_P$5") (pintype "bidirectional"))
      (node (ref "U13") (pin "P$4") (pinfunction "4_P$4") (pintype "bidirectional"))
    )
    (net (code "43") (name "/RLY_5") (class "Default")
      (node (ref "RELAYS") (pin "P$6") (pinfunction "6_P$6") (pintype "bidirectional"))
      (node (ref "U15") (pin "P$4") (pinfunction "4_P$4") (pintype "bidirectional"))
    )
    (net (code "44") (name "/RLY_6") (class "Default")
      (node (ref "RELAYS") (pin "P$7") (pinfunction "7_P$7") (pintype "bidirectional"))
      (node (ref "U17") (pin "P$4") (pinfunction "4_P$4") (pintype "bidirectional"))
    )
    (net (code "45") (name "/RLY_7") (class "Default")
      (node (ref "RELAYS") (pin "P$8") (pinfunction "8_P$8") (pintype "bidirectional"))
      (node (ref "U18") (pin "P$4") (pinfunction "4_P$4") (pintype "bidirectional"))
    )
    (net (code "46") (name "/RS") (class "Default")
      (node (ref "DISP1") (pin "P$12") (pinfunction "RS_P$12") (pintype "bidirectional"))
      (node (ref "R18") (pin "2") (pinfunction "2_2") (pintype "passive"))
    )
    (net (code "47") (name "/RX_PROP") (class "Default")
      (node (ref "PROP_TC") (pin "P$4") (pinfunction "PIN4_P$4") (pintype "bidirectional"))
      (node (ref "PROP_UART") (pin "4") (pinfunction "4_4") (pintype "passive"))
      (node (ref "U1") (pin "38") (pinfunction "P31_38") (pintype "bidirectional"))
    )
    (net (code "48") (name "/R{slash}W") (class "Default")
      (node (ref "DISP1") (pin "P$9") (pinfunction "R/W_P$9") (pintype "bidirectional"))
      (node (ref "R14") (pin "2") (pinfunction "2_2") (pintype "passive"))
    )
    (net (code "49") (name "/SCL") (class "Default")
      (node (ref "R15") (pin "1") (pinfunction "1_1") (pintype "passive"))
      (node (ref "U1") (pin "35") (pinfunction "P28_35") (pintype "bidirectional"))
      (node (ref "U7") (pin "6") (pinfunction "SCL_6") (pintype "bidirectional"))
    )
    (net (code "50") (name "/SCL_1") (class "Default")
      (node (ref "R12") (pin "1") (pinfunction "1_1") (pintype "passive"))
      (node (ref "U1") (pin "11") (pinfunction "P10_11") (pintype "bidirectional"))
      (node (ref "U27") (pin "P$4") (pinfunction "SCL/SCKL_P$4") (pintype "bidirectional"))
      (node (ref "U29") (pin "P$5") (pinfunction "SCL_P$5") (pintype "bidirectional"))
    )
    (net (code "51") (name "/SDA") (class "Default")
      (node (ref "R16") (pin "1") (pinfunction "1_1") (pintype "passive"))
      (node (ref "U1") (pin "36") (pinfunction "P29_36") (pintype "bidirectional"))
      (node (ref "U7") (pin "5") (pinfunction "SDA_5") (pintype "bidirectional"))
    )
    (net (code "52") (name "/SDA_1") (class "Default")
      (node (ref "R13") (pin "1") (pinfunction "1_1") (pintype "passive"))
      (node (ref "U1") (pin "10") (pinfunction "P9_10") (pintype "bidirectional"))
      (node (ref "U27") (pin "P$6") (pinfunction "SDA/MOSI_P$6") (pintype "bidirectional"))
      (node (ref "U29") (pin "P$6") (pinfunction "SDA_P$6") (pintype "bidirectional"))
    )
    (net (code "53") (name "/SW_D") (class "Default")
      (node (ref "R9") (pin "2") (pinfunction "2_2") (pintype "passive"))
      (node (ref "SW3") (pin "P$1") (pinfunction "P$1_P$1") (pintype "bidirectional"))
      (node (ref "SW_D") (pin "P$1") (pinfunction "PIN1_P$1") (pintype "bidirectional"))
      (node (ref "U1") (pin "22") (pinfunction "P19_22") (pintype "bidirectional"))
    )
    (net (code "54") (name "/SW_S") (class "Default")
      (node (ref "R10") (pin "2") (pinfunction "2_2") (pintype "passive"))
      (node (ref "SW2") (pin "P$1") (pinfunction "P$1_P$1") (pintype "bidirectional"))
      (node (ref "SW_S") (pin "P$1") (pinfunction "PIN1_P$1") (pintype "bidirectional"))
      (node (ref "U1") (pin "23") (pinfunction "P20_23") (pintype "bidirectional"))
    )
    (net (code "55") (name "/SW_U") (class "Default")
      (node (ref "R17") (pin "2") (pinfunction "2_2") (pintype "passive"))
      (node (ref "SW1") (pin "P$1") (pinfunction "P$1_P$1") (pintype "bidirectional"))
      (node (ref "SW_U") (pin "P$1") (pinfunction "PIN1_P$1") (pintype "bidirectional"))
      (node (ref "U1") (pin "24") (pinfunction "P21_24") (pintype "bidirectional"))
    )
    (net (code "56") (name "/T+_0") (class "Default")
      (node (ref "C33") (pin "1") (pinfunction "1_1") (pintype "passive"))
      (node (ref "D8") (pin "1") (pinfunction "1_1") (pintype "bidirectional"))
      (node (ref "J1") (pin "P$1") (pinfunction "PIN1_P$1") (pintype "bidirectional"))
      (node (ref "U9") (pin "3") (pinfunction "T+_3") (pintype "bidirectional"))
    )
    (net (code "57") (name "/T+_1") (class "Default")
      (node (ref "C35") (pin "1") (pinfunction "1_1") (pintype "passive"))
      (node (ref "D9") (pin "1") (pinfunction "1_1") (pintype "bidirectional"))
      (node (ref "J2") (pin "P$1") (pinfunction "PIN1_P$1") (pintype "bidirectional"))
      (node (ref "U10") (pin "3") (pinfunction "T+_3") (pintype "bidirectional"))
    )
    (net (code "58") (name "/T+_2") (class "Default")
      (node (ref "C39") (pin "1") (pinfunction "1_1") (pintype "passive"))
      (node (ref "D7") (pin "1") (pinfunction "1_1") (pintype "bidirectional"))
      (node (ref "J3") (pin "P$1") (pinfunction "PIN1_P$1") (pintype "bidirectional"))
      (node (ref "U11") (pin "3") (pinfunction "T+_3") (pintype "bidirectional"))
    )
    (net (code "59") (name "/T+_3") (class "Default")
      (node (ref "C12") (pin "1") (pinfunction "1_1") (pintype "passive"))
      (node (ref "D10") (pin "1") (pinfunction "1_1") (pintype "bidirectional"))
      (node (ref "J4") (pin "P$1") (pinfunction "PIN1_P$1") (pintype "bidirectional"))
      (node (ref "U4") (pin "3") (pinfunction "T+_3") (pintype "bidirectional"))
    )
    (net (code "60") (name "/T-_0") (class "Default")
      (node (ref "C33") (pin "2") (pinfunction "2_2") (pintype "passive"))
      (node (ref "D8") (pin "2") (pinfunction "2_2") (pintype "bidirectional"))
      (node (ref "J1") (pin "P$2") (pinfunction "PIN2_P$2") (pintype "bidirectional"))
      (node (ref "U9") (pin "2") (pinfunction "T-_2") (pintype "bidirectional"))
    )
    (net (code "61") (name "/T-_1") (class "Default")
      (node (ref "C35") (pin "2") (pinfunction "2_2") (pintype "passive"))
      (node (ref "D9") (pin "2") (pinfunction "2_2") (pintype "bidirectional"))
      (node (ref "J2") (pin "P$2") (pinfunction "PIN2_P$2") (pintype "bidirectional"))
      (node (ref "U10") (pin "2") (pinfunction "T-_2") (pintype "bidirectional"))
    )
    (net (code "62") (name "/T-_2") (class "Default")
      (node (ref "C39") (pin "2") (pinfunction "2_2") (pintype "passive"))
      (node (ref "D7") (pin "2") (pinfunction "2_2") (pintype "bidirectional"))
      (node (ref "J3") (pin "P$2") (pinfunction "PIN2_P$2") (pintype "bidirectional"))
      (node (ref "U11") (pin "2") (pinfunction "T-_2") (pintype "bidirectional"))
    )
    (net (code "63") (name "/T-_3") (class "Default")
      (node (ref "C12") (pin "2") (pinfunction "2_2") (pintype "passive"))
      (node (ref "D10") (pin "2") (pinfunction "2_2") (pintype "bidirectional"))
      (node (ref "J4") (pin "P$2") (pinfunction "PIN2_P$2") (pintype "bidirectional"))
      (node (ref "U4") (pin "2") (pinfunction "T-_2") (pintype "bidirectional"))
    )
    (net (code "64") (name "/TC_CS_0") (class "Default")
      (node (ref "U1") (pin "25") (pinfunction "P22_25") (pintype "bidirectional"))
      (node (ref "U9") (pin "6") (pinfunction "~{CS}_6") (pintype "bidirectional"))
    )
    (net (code "65") (name "/TC_CS_1") (class "Default")
      (node (ref "U1") (pin "26") (pinfunction "P23_26") (pintype "bidirectional"))
      (node (ref "U10") (pin "6") (pinfunction "~{CS}_6") (pintype "bidirectional"))
    )
    (net (code "66") (name "/TC_CS_2") (class "Default")
      (node (ref "U1") (pin "31") (pinfunction "P24_31") (pintype "bidirectional"))
      (node (ref "U11") (pin "6") (pinfunction "~{CS}_6") (pintype "bidirectional"))
    )
    (net (code "67") (name "/TC_CS_3") (class "Default")
      (node (ref "U1") (pin "32") (pinfunction "P25_32") (pintype "bidirectional"))
      (node (ref "U4") (pin "6") (pinfunction "~{CS}_6") (pintype "bidirectional"))
    )
    (net (code "68") (name "/TC_SCK") (class "Default")
      (node (ref "U1") (pin "34") (pinfunction "P27_34") (pintype "bidirectional"))
      (node (ref "U10") (pin "5") (pinfunction "SCK_5") (pintype "bidirectional"))
      (node (ref "U11") (pin "5") (pinfunction "SCK_5") (pintype "bidirectional"))
      (node (ref "U4") (pin "5") (pinfunction "SCK_5") (pintype "bidirectional"))
      (node (ref "U9") (pin "5") (pinfunction "SCK_5") (pintype "bidirectional"))
    )
    (net (code "69") (name "/TC_SO") (class "Default")
      (node (ref "U1") (pin "33") (pinfunction "P26_33") (pintype "bidirectional"))
      (node (ref "U10") (pin "7") (pinfunction "SO_7") (pintype "bidirectional"))
      (node (ref "U11") (pin "7") (pinfunction "SO_7") (pintype "bidirectional"))
      (node (ref "U4") (pin "7") (pinfunction "SO_7") (pintype "bidirectional"))
      (node (ref "U9") (pin "7") (pinfunction "SO_7") (pintype "bidirectional"))
    )
    (net (code "70") (name "/TX_PROP") (class "Default")
      (node (ref "PROP_TC") (pin "P$3") (pinfunction "PIN3_P$3") (pintype "bidirectional"))
      (node (ref "PROP_UART") (pin "5") (pinfunction "5_5") (pintype "passive"))
      (node (ref "U1") (pin "37") (pinfunction "P30_37") (pintype "bidirectional"))
    )
    (net (code "71") (name "/X0") (class "Default")
      (node (ref "U1") (pin "29") (pinfunction "X0_29") (pintype "bidirectional"))
      (node (ref "X1") (pin "P$1") (pinfunction "X0_P$1") (pintype "bidirectional"))
    )
    (net (code "72") (name "/X1") (class "Default")
      (node (ref "U1") (pin "28") (pinfunction "X1_28") (pintype "bidirectional"))
      (node (ref "X1") (pin "P$3") (pinfunction "X1_P$3") (pintype "bidirectional"))
    )
    (net (code "73") (name "/~{RES}_PROP") (class "Default")
      (node (ref "C5") (pin "1") (pinfunction "1_1") (pintype "passive"))
      (node (ref "PROP_TC") (pin "P$6") (pinfunction "PIN6_P$6") (pintype "bidirectional"))
      (node (ref "PROP_UART") (pin "6") (pinfunction "6_6") (pintype "passive"))
    )
    (net (code "74") (name "3.3V") (class "Default")
      (node (ref "C1") (pin "1") (pinfunction "1_1") (pintype "passive"))
      (node (ref "C11") (pin "1") (pinfunction "1_1") (pintype "passive"))
      (node (ref "C2") (pin "1") (pinfunction "1_1") (pintype "passive"))
      (node (ref "C22") (pin "1") (pinfunction "1_1") (pintype "passive"))
      (node (ref "C23") (pin "1") (pinfunction "1_1") (pintype "passive"))
      (node (ref "C24") (pin "POS") (pinfunction "POS_POS") (pintype "bidirectional"))
      (node (ref "C25") (pin "1") (pinfunction "1_1") (pintype "passive"))
      (node (ref "C3") (pin "1") (pinfunction "1_1") (pintype "passive"))
      (node (ref "C31") (pin "1") (pinfunction "1_1") (pintype "passive"))
      (node (ref "C32") (pin "1") (pinfunction "1_1") (pintype "passive"))
      (node (ref "C34") (pin "1") (pinfunction "1_1") (pintype "passive"))
      (node (ref "C36") (pin "1") (pinfunction "1_1") (pintype "passive"))
      (node (ref "C37") (pin "1") (pinfunction "1_1") (pintype "passive"))
      (node (ref "C38") (pin "1") (pinfunction "1_1") (pintype "passive"))
      (node (ref "C4") (pin "1") (pinfunction "1_1") (pintype "passive"))
      (node (ref "C41") (pin "1") (pinfunction "1_1") (pintype "passive"))
      (node (ref "C43") (pin "1") (pinfunction "1_1") (pintype "passive"))
      (node (ref "C7") (pin "1") (pinfunction "1_1") (pintype "passive"))
      (node (ref "C8") (pin "1") (pinfunction "1_1") (pintype "passive"))
      (node (ref "C9") (pin "1") (pinfunction "1_1") (pintype "passive"))
      (node (ref "R1") (pin "2") (pinfunction "2_2") (pintype "passive"))
      (node (ref "R10") (pin "1") (pinfunction "1_1") (pintype "passive"))
      (node (ref "R11") (pin "2") (pinfunction "2_2") (pintype "passive"))
      (node (ref "R12") (pin "2") (pinfunction "2_2") (pintype "passive"))
      (node (ref "R13") (pin "2") (pinfunction "2_2") (pintype "passive"))
      (node (ref "R15") (pin "2") (pinfunction "2_2") (pintype "passive"))
      (node (ref "R16") (pin "2") (pinfunction "2_2") (pintype "passive"))
      (node (ref "R17") (pin "1") (pinfunction "1_1") (pintype "passive"))
      (node (ref "R28") (pin "P$2") (pinfunction "P$2_P$2") (pintype "passive"))
      (node (ref "R29") (pin "P$2") (pinfunction "P$2_P$2") (pintype "passive"))
      (node (ref "R30") (pin "P$2") (pinfunction "P$2_P$2") (pintype "passive"))
      (node (ref "R31") (pin "P$2") (pinfunction "P$2_P$2") (pintype "passive"))
      (node (ref "R32") (pin "P$2") (pinfunction "P$2_P$2") (pintype "passive"))
      (node (ref "R33") (pin "P$2") (pinfunction "P$2_P$2") (pintype "passive"))
      (node (ref "R34") (pin "P$2") (pinfunction "P$2_P$2") (pintype "passive"))
      (node (ref "R35") (pin "P$2") (pinfunction "P$2_P$2") (pintype "passive"))
      (node (ref "R9") (pin "1") (pinfunction "1_1") (pintype "passive"))
      (node (ref "TP2") (pin "P$1") (pinfunction "P$1_P$1") (pintype "bidirectional"))
      (node (ref "U1") (pin "18") (pinfunction "VDD_18") (pintype "power_in"))
      (node (ref "U1") (pin "30") (pinfunction "VDD_30") (pintype "power_in"))
      (node (ref "U1") (pin "40") (pinfunction "VDD_40") (pintype "power_in"))
      (node (ref "U1") (pin "8") (pinfunction "VDD_8") (pintype "power_in"))
      (node (ref "U10") (pin "4") (pinfunction "VCC_4") (pintype "bidirectional"))
      (node (ref "U11") (pin "4") (pinfunction "VCC_4") (pintype "bidirectional"))
      (node (ref "U14") (pin "10") (pinfunction "MR_10") (pintype "bidirectional"))
      (node (ref "U14") (pin "16") (pinfunction "VCC_16") (pintype "bidirectional"))
      (node (ref "U16") (pin "16") (pinfunction "VCC_16") (pintype "bidirectional"))
      (node (ref "U27") (pin "P$1") (pinfunction "VDDIO_P$1") (pintype "bidirectional"))
      (node (ref "U27") (pin "P$14") (pinfunction "VDD_P$14") (pintype "bidirectional"))
      (node (ref "U28") (pin "P$8") (pinfunction "VDD2_P$8") (pintype "bidirectional"))
      (node (ref "U29") (pin "P$8") (pinfunction "VCC_P$8") (pintype "bidirectional"))
      (node (ref "U4") (pin "4") (pinfunction "VCC_4") (pintype "bidirectional"))
      (node (ref "U6") (pin "2") (pinfunction "OUT_2") (pintype "bidirectional"))
      (node (ref "U6") (pin "PAD") (pinfunction "OUT_PAD") (pintype "bidirectional"))
      (node (ref "U7") (pin "8") (pinfunction "VCC_8") (pintype "bidirectional"))
      (node (ref "U9") (pin "4") (pinfunction "VCC_4") (pintype "bidirectional"))
    )
    (net (code "75") (name "5.0V") (class "Default")
      (node (ref "C13") (pin "1") (pinfunction "1_1") (pintype "passive"))
      (node (ref "C15") (pin "POS") (pinfunction "POS_POS") (pintype "bidirectional"))
      (node (ref "C16") (pin "1") (pinfunction "1_1") (pintype "passive"))
      (node (ref "C17") (pin "1") (pinfunction "1_1") (pintype "passive"))
      (node (ref "C28") (pin "POS") (pinfunction "POS_POS") (pintype "bidirectional"))
      (node (ref "C6") (pin "1") (pinfunction "1_1") (pintype "passive"))
      (node (ref "DISP1") (pin "P$13") (pinfunction "VCC_P$13") (pintype "bidirectional"))
      (node (ref "L3") (pin "1") (pinfunction "P$1_1") (pintype "bidirectional"))
      (node (ref "TP1") (pin "P$1") (pinfunction "P$1_P$1") (pintype "bidirectional"))
      (node (ref "U5") (pin "P$6") (pinfunction "FB_P$6") (pintype "bidirectional"))
      (node (ref "U6") (pin "3") (pinfunction "IN_3") (pintype "bidirectional"))
    )
    (net (code "76") (name "12V CLEAN") (class "Default")
      (node (ref "C10") (pin "1") (pinfunction "1_1") (pintype "passive"))
      (node (ref "C14") (pin "1") (pinfunction "1_1") (pintype "passive"))
      (node (ref "C20") (pin "POS") (pinfunction "POS_POS") (pintype "bidirectional"))
      (node (ref "C21") (pin "POS") (pinfunction "POS_POS") (pintype "bidirectional"))
      (node (ref "C29") (pin "1") (pinfunction "1_1") (pintype "passive"))
      (node (ref "C30") (pin "1") (pinfunction "1_1") (pintype "passive"))
      (node (ref "L2") (pin "2") (pinfunction "2_2") (pintype "bidirectional"))
      (node (ref "R2") (pin "1") (pinfunction "1_1") (pintype "passive"))
      (node (ref "TP3") (pin "P$1") (pinfunction "P$1_P$1") (pintype "bidirectional"))
      (node (ref "U5") (pin "P$2") (pinfunction "VIN_P$2") (pintype "bidirectional"))
    )
    (net (code "77") (name "12V_BATT_ON") (class "Default")
      (node (ref "C18") (pin "POS") (pinfunction "POS_POS") (pintype "bidirectional"))
      (node (ref "C19") (pin "POS") (pinfunction "POS_POS") (pintype "bidirectional"))
      (node (ref "C44") (pin "1") (pinfunction "1_1") (pintype "passive"))
      (node (ref "D2") (pin "PAD-4") (pinfunction "CATHODE_PAD-4") (pintype "bidirectional"))
      (node (ref "L2") (pin "1") (pinfunction "1_1") (pintype "bidirectional"))
      (node (ref "TP4") (pin "P$1") (pinfunction "P$1_P$1") (pintype "bidirectional"))
      (node (ref "U30") (pin "P$1") (pinfunction "VIN_P$1") (pintype "bidirectional"))
    )
    (net (code "78") (name "CHASSIS_GND") (class "Default")
      (node (ref "BOARD_PWR") (pin "P$2") (pinfunction "PIN2_P$2") (pintype "bidirectional"))
      (node (ref "C18") (pin "NEG") (pinfunction "NEG_NEG") (pintype "bidirectional"))
      (node (ref "C19") (pin "NEG") (pinfunction "NEG_NEG") (pintype "bidirectional"))
      (node (ref "C44") (pin "2") (pinfunction "2_2") (pintype "passive"))
      (node (ref "C45") (pin "2") (pinfunction "2_2") (pintype "passive"))
      (node (ref "L2") (pin "4") (pinfunction "4_4") (pintype "bidirectional"))
      (node (ref "R44") (pin "P$1") (pinfunction "P$1_P$1") (pintype "passive"))
      (node (ref "TP6") (pin "P$1") (pinfunction "P$1_P$1") (pintype "bidirectional"))
      (node (ref "TVS1") (pin "P$1") (pinfunction "P$1_P$1") (pintype "bidirectional"))
      (node (ref "U12") (pin "P$3") (pinfunction "3_P$3") (pintype "bidirectional"))
      (node (ref "U13") (pin "P$3") (pinfunction "3_P$3") (pintype "bidirectional"))
      (node (ref "U15") (pin "P$3") (pinfunction "3_P$3") (pintype "bidirectional"))
      (node (ref "U17") (pin "P$3") (pinfunction "3_P$3") (pintype "bidirectional"))
      (node (ref "U18") (pin "P$3") (pinfunction "3_P$3") (pintype "bidirectional"))
      (node (ref "U19") (pin "P$2") (pinfunction "CATHODE_P$2") (pintype "bidirectional"))
      (node (ref "U2") (pin "P$3") (pinfunction "3_P$3") (pintype "bidirectional"))
      (node (ref "U20") (pin "P$2") (pinfunction "CATHODE_P$2") (pintype "bidirectional"))
      (node (ref "U21") (pin "P$2") (pinfunction "CATHODE_P$2") (pintype "bidirectional"))
      (node (ref "U22") (pin "P$2") (pinfunction "CATHODE_P$2") (pintype "bidirectional"))
      (node (ref "U23") (pin "P$2") (pinfunction "CATHODE_P$2") (pintype "bidirectional"))
      (node (ref "U24") (pin "P$2") (pinfunction "CATHODE_P$2") (pintype "bidirectional"))
      (node (ref "U25") (pin "P$2") (pinfunction "CATHODE_P$2") (pintype "bidirectional"))
      (node (ref "U26") (pin "P$2") (pinfunction "CATHODE_P$2") (pintype "bidirectional"))
      (node (ref "U28") (pin "P$3") (pinfunction "SHDN_P$3") (pintype "bidirectional"))
      (node (ref "U28") (pin "P$4") (pinfunction "GND1_P$4") (pintype "bidirectional"))
      (node (ref "U3") (pin "P$3") (pinfunction "3_P$3") (pintype "bidirectional"))
      (node (ref "U30") (pin "P$3") (pinfunction "GND/ADJ_P$3") (pintype "bidirectional"))
      (node (ref "U30") (pin "P$4") (pinfunction "GND/ADJ_P$4") (pintype "bidirectional"))
      (node (ref "U8") (pin "P$3") (pinfunction "3_P$3") (pintype "bidirectional"))
    )
    (net (code "79") (name "GND") (class "Default")
      (node (ref "3.3V_PWR") (pin "CATHODE") (pinfunction "CATHODE_CATHODE") (pintype "bidirectional"))
      (node (ref "C1") (pin "2") (pinfunction "2_2") (pintype "passive"))
      (node (ref "C10") (pin "2") (pinfunction "2_2") (pintype "passive"))
      (node (ref "C11") (pin "2") (pinfunction "2_2") (pintype "passive"))
      (node (ref "C13") (pin "2") (pinfunction "2_2") (pintype "passive"))
      (node (ref "C14") (pin "2") (pinfunction "2_2") (pintype "passive"))
      (node (ref "C15") (pin "NEG") (pinfunction "NEG_NEG") (pintype "bidirectional"))
      (node (ref "C16") (pin "2") (pinfunction "2_2") (pintype "passive"))
      (node (ref "C17") (pin "2") (pinfunction "2_2") (pintype "passive"))
      (node (ref "C2") (pin "2") (pinfunction "2_2") (pintype "passive"))
      (node (ref "C20") (pin "NEG") (pinfunction "NEG_NEG") (pintype "bidirectional"))
      (node (ref "C21") (pin "NEG") (pinfunction "NEG_NEG") (pintype "bidirectional"))
      (node (ref "C22") (pin "2") (pinfunction "2_2") (pintype "passive"))
      (node (ref "C23") (pin "2") (pinfunction "2_2") (pintype "passive"))
      (node (ref "C24") (pin "NEG") (pinfunction "NEG_NEG") (pintype "bidirectional"))
      (node (ref "C25") (pin "2") (pinfunction "2_2") (pintype "passive"))
      (node (ref "C26") (pin "2") (pinfunction "2_2") (pintype "passive"))
      (node (ref "C28") (pin "NEG") (pinfunction "NEG_NEG") (pintype "bidirectional"))
      (node (ref "C29") (pin "2") (pinfunction "2_2") (pintype "passive"))
      (node (ref "C3") (pin "2") (pinfunction "2_2") (pintype "passive"))
      (node (ref "C30") (pin "2") (pinfunction "2_2") (pintype "passive"))
      (node (ref "C31") (pin "2") (pinfunction "2_2") (pintype "passive"))
      (node (ref "C32") (pin "2") (pinfunction "2_2") (pintype "passive"))
      (node (ref "C34") (pin "2") (pinfunction "2_2") (pintype "passive"))
      (node (ref "C36") (pin "2") (pinfunction "2_2") (pintype "passive"))
      (node (ref "C37") (pin "2") (pinfunction "2_2") (pintype "passive"))
      (node (ref "C38") (pin "2") (pinfunction "2_2") (pintype "passive"))
      (node (ref "C4") (pin "2") (pinfunction "2_2") (pintype "passive"))
      (node (ref "C40") (pin "2") (pinfunction "2_2") (pintype "passive"))
      (node (ref "C41") (pin "2") (pinfunction "2_2") (pintype "passive"))
      (node (ref "C42") (pin "2") (pinfunction "2_2") (pintype "passive"))
      (node (ref "C43") (pin "2") (pinfunction "2_2") (pintype "passive"))
      (node (ref "C6") (pin "2") (pinfunction "2_2") (pintype "passive"))
      (node (ref "C7") (pin "2") (pinfunction "2_2") (pintype "passive"))
      (node (ref "C8") (pin "2") (pinfunction "2_2") (pintype "passive"))
      (node (ref "C9") (pin "2") (pinfunction "2_2") (pintype "passive"))
      (node (ref "D10") (pin "3") (pinfunction "3_3") (pintype "bidirectional"))
      (node (ref "D3") (pin "A") (pinfunction "ANODE_A") (pintype "bidirectional"))
      (node (ref "D7") (pin "3") (pinfunction "3_3") (pintype "bidirectional"))
      (node (ref "D8") (pin "3") (pinfunction "3_3") (pintype "bidirectional"))
      (node (ref "D9") (pin "3") (pinfunction "3_3") (pintype "bidirectional"))
      (node (ref "DISP1") (pin "P$14") (pinfunction "GND_P$14") (pintype "bidirectional"))
      (node (ref "DISP1") (pin "P$5") (pinfunction "D2_P$5") (pintype "bidirectional"))
      (node (ref "DISP1") (pin "P$6") (pinfunction "D3_P$6") (pintype "bidirectional"))
      (node (ref "DISP1") (pin "P$7") (pinfunction "D0_P$7") (pintype "bidirectional"))
      (node (ref "DISP1") (pin "P$8") (pinfunction "D1_P$8") (pintype "bidirectional"))
      (node (ref "L2") (pin "3") (pinfunction "3_3") (pintype "bidirectional"))
      (node (ref "PROP_TC") (pin "P$5") (pinfunction "PIN5_P$5") (pintype "bidirectional"))
      (node (ref "PROP_UART") (pin "1") (pinfunction "1_1") (pintype "passive"))
      (node (ref "SW1") (pin "P$4") (pinfunction "P$4_P$4") (pintype "bidirectional"))
      (node (ref "SW2") (pin "P$4") (pinfunction "P$4_P$4") (pintype "bidirectional"))
      (node (ref "SW3") (pin "P$4") (pinfunction "P$4_P$4") (pintype "bidirectional"))
      (node (ref "SW_D") (pin "P$2") (pinfunction "PIN2_P$2") (pintype "bidirectional"))
      (node (ref "SW_S") (pin "P$2") (pinfunction "PIN2_P$2") (pintype "bidirectional"))
      (node (ref "SW_U") (pin "P$2") (pinfunction "PIN2_P$2") (pintype "bidirectional"))
      (node (ref "TP5") (pin "P$1") (pinfunction "P$1_P$1") (pintype "bidirectional"))
      (node (ref "U1") (pin "17") (pinfunction "VSS_17") (pintype "power_in"))
      (node (ref "U1") (pin "27") (pinfunction "VSS_27") (pintype "power_in"))
      (node (ref "U1") (pin "39") (pinfunction "VSS_39") (pintype "power_in"))
      (node (ref "U1") (pin "5") (pinfunction "VSS_5") (pintype "power_in"))
      (node (ref "U1") (pin "6") (pinfunction "BOE'_6") (pintype "bidirectional"))
      (node (ref "U10") (pin "1") (pinfunction "GND_1") (pintype "bidirectional"))
      (node (ref "U11") (pin "1") (pinfunction "GND_1") (pintype "bidirectional"))
      (node (ref "U12") (pin "P$2") (pinfunction "CATHODE_P$2") (pintype "bidirectional"))
      (node (ref "U13") (pin "P$2") (pinfunction "CATHODE_P$2") (pintype "bidirectional"))
      (node (ref "U14") (pin "13") (pinfunction "OE_13") (pintype "bidirectional"))
      (node (ref "U14") (pin "8") (pinfunction "GND_8") (pintype "bidirectional"))
      (node (ref "U15") (pin "P$2") (pinfunction "CATHODE_P$2") (pintype "bidirectional"))
      (node (ref "U16") (pin "15") (pinfunction "C_INH_15") (pintype "bidirectional"))
      (node (ref "U16") (pin "8") (pinfunction "GND_8") (pintype "bidirectional"))
      (node (ref "U17") (pin "P$2") (pinfunction "CATHODE_P$2") (pintype "bidirectional"))
      (node (ref "U18") (pin "P$2") (pinfunction "CATHODE_P$2") (pintype "bidirectional"))
      (node (ref "U19") (pin "P$3") (pinfunction "3_P$3") (pintype "bidirectional"))
      (node (ref "U2") (pin "P$2") (pinfunction "CATHODE_P$2") (pintype "bidirectional"))
      (node (ref "U20") (pin "P$3") (pinfunction "3_P$3") (pintype "bidirectional"))
      (node (ref "U21") (pin "P$3") (pinfunction "3_P$3") (pintype "bidirectional"))
      (node (ref "U22") (pin "P$3") (pinfunction "3_P$3") (pintype "bidirectional"))
      (node (ref "U23") (pin "P$3") (pinfunction "3_P$3") (pintype "bidirectional"))
      (node (ref "U24") (pin "P$3") (pinfunction "3_P$3") (pintype "bidirectional"))
      (node (ref "U25") (pin "P$3") (pinfunction "3_P$3") (pintype "bidirectional"))
      (node (ref "U26") (pin "P$3") (pinfunction "3_P$3") (pintype "bidirectional"))
      (node (ref "U27") (pin "P$10") (pinfunction "SA1/CS_B_P$10") (pintype "bidirectional"))
      (node (ref "U27") (pin "P$12") (pinfunction "GND_P$12") (pintype "bidirectional"))
      (node (ref "U27") (pin "P$13") (pinfunction "GND_P$13") (pintype "bidirectional"))
      (node (ref "U27") (pin "P$16") (pinfunction "RST_P$16") (pintype "bidirectional"))
      (node (ref "U27") (pin "P$3") (pinfunction "GND_P$3") (pintype "bidirectional"))
      (node (ref "U27") (pin "P$5") (pinfunction "GND_P$5") (pintype "bidirectional"))
      (node (ref "U27") (pin "P$7") (pinfunction "SA0/MISO_P$7") (pintype "bidirectional"))
      (node (ref "U28") (pin "P$5") (pinfunction "GND2_P$5") (pintype "bidirectional"))
      (node (ref "U28") (pin "P$6") (pinfunction "VOUT-_P$6") (pintype "bidirectional"))
      (node (ref "U29") (pin "P$7") (pinfunction "GND_P$7") (pintype "bidirectional"))
      (node (ref "U3") (pin "P$2") (pinfunction "CATHODE_P$2") (pintype "bidirectional"))
      (node (ref "U4") (pin "1") (pinfunction "GND_1") (pintype "bidirectional"))
      (node (ref "U5") (pin "P$4") (pinfunction "GND_P$4") (pintype "bidirectional"))
      (node (ref "U5") (pin "PAD") (pinfunction "GND_PAD") (pintype "bidirectional"))
      (node (ref "U6") (pin "1") (pinfunction "GND_1") (pintype "bidirectional"))
      (node (ref "U7") (pin "2") (pinfunction "A1_2") (pintype "bidirectional"))
      (node (ref "U7") (pin "3") (pinfunction "A2_3") (pintype "bidirectional"))
      (node (ref "U7") (pin "4") (pinfunction "GND_4") (pintype "bidirectional"))
      (node (ref "U7") (pin "7") (pinfunction "WP_7") (pintype "bidirectional"))
      (node (ref "U8") (pin "P$2") (pinfunction "CATHODE_P$2") (pintype "bidirectional"))
      (node (ref "U9") (pin "1") (pinfunction "GND_1") (pintype "bidirectional"))
      (node (ref "X1") (pin "P$2") (pinfunction "GND_P$2") (pintype "bidirectional"))
      (node (ref "X1") (pin "P$4") (pinfunction "GND_P$4") (pintype "bidirectional"))
    )
    (net (code "80") (name "Net-(3.3V_PWR-PadANODE)") (class "Default")
      (node (ref "3.3V_PWR") (pin "ANODE") (pinfunction "ANODE_ANODE") (pintype "bidirectional"))
      (node (ref "R11") (pin "1") (pinfunction "1_1") (pintype "passive"))
    )
    (net (code "81") (name "Net-(D3-CATHODE)") (class "Default")
      (node (ref "C27") (pin "2") (pinfunction "2_2") (pintype "passive"))
      (node (ref "D3") (pin "C") (pinfunction "CATHODE_C") (pintype "bidirectional"))
      (node (ref "L3") (pin "2") (pinfunction "P$2_2") (pintype "bidirectional"))
      (node (ref "U5") (pin "P$1") (pinfunction "SW_P$1") (pintype "bidirectional"))
    )
    (net (code "82") (name "Net-(J5-PIN1)") (class "Default")
      (node (ref "J5") (pin "P$1") (pinfunction "PIN1_P$1") (pintype "bidirectional"))
      (node (ref "R45") (pin "P$1") (pinfunction "P$1_P$1") (pintype "passive"))
    )
    (net (code "83") (name "Net-(SWITCHS-1)") (class "Default")
      (node (ref "R27") (pin "P$2") (pinfunction "P$2_P$2") (pintype "passive"))
      (node (ref "SWITCHS") (pin "P$1") (pinfunction "1_P$1") (pintype "bidirectional"))
    )
    (net (code "84") (name "Net-(SWITCHS-2)") (class "Default")
      (node (ref "R36") (pin "P$2") (pinfunction "P$2_P$2") (pintype "passive"))
      (node (ref "SWITCHS") (pin "P$2") (pinfunction "2_P$2") (pintype "bidirectional"))
    )
    (net (code "85") (name "Net-(SWITCHS-3)") (class "Default")
      (node (ref "R37") (pin "P$2") (pinfunction "P$2_P$2") (pintype "passive"))
      (node (ref "SWITCHS") (pin "P$3") (pinfunction "3_P$3") (pintype "bidirectional"))
    )
    (net (code "86") (name "Net-(SWITCHS-4)") (class "Default")
      (node (ref "R38") (pin "P$2") (pinfunction "P$2_P$2") (pintype "passive"))
      (node (ref "SWITCHS") (pin "P$4") (pinfunction "4_P$4") (pintype "bidirectional"))
    )
    (net (code "87") (name "Net-(SWITCHS-5)") (class "Default")
      (node (ref "R39") (pin "P$2") (pinfunction "P$2_P$2") (pintype "passive"))
      (node (ref "SWITCHS") (pin "P$5") (pinfunction "5_P$5") (pintype "bidirectional"))
    )
    (net (code "88") (name "Net-(SWITCHS-6)") (class "Default")
      (node (ref "R40") (pin "P$2") (pinfunction "P$2_P$2") (pintype "passive"))
      (node (ref "SWITCHS") (pin "P$6") (pinfunction "6_P$6") (pintype "bidirectional"))
    )
    (net (code "89") (name "Net-(SWITCHS-7)") (class "Default")
      (node (ref "R41") (pin "P$2") (pinfunction "P$2_P$2") (pintype "passive"))
      (node (ref "SWITCHS") (pin "P$7") (pinfunction "7_P$7") (pintype "bidirectional"))
    )
    (net (code "90") (name "Net-(SWITCHS-8)") (class "Default")
      (node (ref "R42") (pin "P$2") (pinfunction "P$2_P$2") (pintype "passive"))
      (node (ref "SWITCHS") (pin "P$8") (pinfunction "8_P$8") (pintype "bidirectional"))
    )
    (net (code "91") (name "Net-(U2-ANODE)") (class "Default")
      (node (ref "R19") (pin "P$2") (pinfunction "P$2_P$2") (pintype "passive"))
      (node (ref "U2") (pin "P$1") (pinfunction "ANODE_P$1") (pintype "bidirectional"))
    )
    (net (code "92") (name "Net-(U3-ANODE)") (class "Default")
      (node (ref "R20") (pin "P$2") (pinfunction "P$2_P$2") (pintype "passive"))
      (node (ref "U3") (pin "P$1") (pinfunction "ANODE_P$1") (pintype "bidirectional"))
    )
    (net (code "93") (name "Net-(U5-BOOT)") (class "Default")
      (node (ref "C27") (pin "1") (pinfunction "1_1") (pintype "passive"))
      (node (ref "U5") (pin "P$3") (pinfunction "BOOT_P$3") (pintype "bidirectional"))
    )
    (net (code "94") (name "Net-(U5-EN)") (class "Default")
      (node (ref "R2") (pin "2") (pinfunction "2_2") (pintype "passive"))
      (node (ref "U5") (pin "P$7") (pinfunction "EN_P$7") (pintype "bidirectional"))
    )
    (net (code "95") (name "Net-(U8-ANODE)") (class "Default")
      (node (ref "R21") (pin "P$2") (pinfunction "P$2_P$2") (pintype "passive"))
      (node (ref "U8") (pin "P$1") (pinfunction "ANODE_P$1") (pintype "bidirectional"))
    )
    (net (code "96") (name "Net-(U12-ANODE)") (class "Default")
      (node (ref "R22") (pin "P$2") (pinfunction "P$2_P$2") (pintype "passive"))
      (node (ref "U12") (pin "P$1") (pinfunction "ANODE_P$1") (pintype "bidirectional"))
    )
    (net (code "97") (name "Net-(U13-ANODE)") (class "Default")
      (node (ref "R23") (pin "P$2") (pinfunction "P$2_P$2") (pintype "passive"))
      (node (ref "U13") (pin "P$1") (pinfunction "ANODE_P$1") (pintype "bidirectional"))
    )
    (net (code "98") (name "Net-(U15-ANODE)") (class "Default")
      (node (ref "R24") (pin "P$2") (pinfunction "P$2_P$2") (pintype "passive"))
      (node (ref "U15") (pin "P$1") (pinfunction "ANODE_P$1") (pintype "bidirectional"))
    )
    (net (code "99") (name "Net-(U16-D0)") (class "Default")
      (node (ref "R28") (pin "P$1") (pinfunction "P$1_P$1") (pintype "passive"))
      (node (ref "U16") (pin "11") (pinfunction "D0_11") (pintype "bidirectional"))
      (node (ref "U19") (pin "P$4") (pinfunction "4_P$4") (pintype "bidirectional"))
    )
    (net (code "100") (name "Net-(U16-D1)") (class "Default")
      (node (ref "R29") (pin "P$1") (pinfunction "P$1_P$1") (pintype "passive"))
      (node (ref "U16") (pin "12") (pinfunction "D1_12") (pintype "bidirectional"))
      (node (ref "U20") (pin "P$4") (pinfunction "4_P$4") (pintype "bidirectional"))
    )
    (net (code "101") (name "Net-(U16-D2)") (class "Default")
      (node (ref "R30") (pin "P$1") (pinfunction "P$1_P$1") (pintype "passive"))
      (node (ref "U16") (pin "13") (pinfunction "D2_13") (pintype "bidirectional"))
      (node (ref "U21") (pin "P$4") (pinfunction "4_P$4") (pintype "bidirectional"))
    )
    (net (code "102") (name "Net-(U16-D3)") (class "Default")
      (node (ref "R31") (pin "P$1") (pinfunction "P$1_P$1") (pintype "passive"))
      (node (ref "U16") (pin "14") (pinfunction "D3_14") (pintype "bidirectional"))
      (node (ref "U22") (pin "P$4") (pinfunction "4_P$4") (pintype "bidirectional"))
    )
    (net (code "103") (name "Net-(U16-D4)") (class "Default")
      (node (ref "R32") (pin "P$1") (pinfunction "P$1_P$1") (pintype "passive"))
      (node (ref "U16") (pin "3") (pinfunction "D4_3") (pintype "bidirectional"))
      (node (ref "U23") (pin "P$4") (pinfunction "4_P$4") (pintype "bidirectional"))
    )
    (net (code "104") (name "Net-(U16-D5)") (class "Default")
      (node (ref "R33") (pin "P$1") (pinfunction "P$1_P$1") (pintype "passive"))
      (node (ref "U16") (pin "4") (pinfunction "D5_4") (pintype "bidirectional"))
      (node (ref "U24") (pin "P$4") (pinfunction "4_P$4") (pintype "bidirectional"))
    )
    (net (code "105") (name "Net-(U16-D6)") (class "Default")
      (node (ref "R34") (pin "P$1") (pinfunction "P$1_P$1") (pintype "passive"))
      (node (ref "U16") (pin "5") (pinfunction "D6_5") (pintype "bidirectional"))
      (node (ref "U25") (pin "P$4") (pinfunction "4_P$4") (pintype "bidirectional"))
    )
    (net (code "106") (name "Net-(U16-D7)") (class "Default")
      (node (ref "R35") (pin "P$1") (pinfunction "P$1_P$1") (pintype "passive"))
      (node (ref "U16") (pin "6") (pinfunction "D7_6") (pintype "bidirectional"))
      (node (ref "U26") (pin "P$4") (pinfunction "4_P$4") (pintype "bidirectional"))
    )
    (net (code "107") (name "Net-(U17-ANODE)") (class "Default")
      (node (ref "R25") (pin "P$2") (pinfunction "P$2_P$2") (pintype "passive"))
      (node (ref "U17") (pin "P$1") (pinfunction "ANODE_P$1") (pintype "bidirectional"))
    )
    (net (code "108") (name "Net-(U18-ANODE)") (class "Default")
      (node (ref "R26") (pin "P$2") (pinfunction "P$2_P$2") (pintype "passive"))
      (node (ref "U18") (pin "P$1") (pinfunction "ANODE_P$1") (pintype "bidirectional"))
    )
    (net (code "109") (name "Net-(U19-ANODE)") (class "Default")
      (node (ref "R27") (pin "P$1") (pinfunction "P$1_P$1") (pintype "passive"))
      (node (ref "U19") (pin "P$1") (pinfunction "ANODE_P$1") (pintype "bidirectional"))
    )
    (net (code "110") (name "Net-(U20-ANODE)") (class "Default")
      (node (ref "R36") (pin "P$1") (pinfunction "P$1_P$1") (pintype "passive"))
      (node (ref "U20") (pin "P$1") (pinfunction "ANODE_P$1") (pintype "bidirectional"))
    )
    (net (code "111") (name "Net-(U21-ANODE)") (class "Default")
      (node (ref "R37") (pin "P$1") (pinfunction "P$1_P$1") (pintype "passive"))
      (node (ref "U21") (pin "P$1") (pinfunction "ANODE_P$1") (pintype "bidirectional"))
    )
    (net (code "112") (name "Net-(U22-ANODE)") (class "Default")
      (node (ref "R38") (pin "P$1") (pinfunction "P$1_P$1") (pintype "passive"))
      (node (ref "U22") (pin "P$1") (pinfunction "ANODE_P$1") (pintype "bidirectional"))
    )
    (net (code "113") (name "Net-(U23-ANODE)") (class "Default")
      (node (ref "R39") (pin "P$1") (pinfunction "P$1_P$1") (pintype "passive"))
      (node (ref "U23") (pin "P$1") (pinfunction "ANODE_P$1") (pintype "bidirectional"))
    )
    (net (code "114") (name "Net-(U24-ANODE)") (class "Default")
      (node (ref "R40") (pin "P$1") (pinfunction "P$1_P$1") (pintype "passive"))
      (node (ref "U24") (pin "P$1") (pinfunction "ANODE_P$1") (pintype "bidirectional"))
    )
    (net (code "115") (name "Net-(U25-ANODE)") (class "Default")
      (node (ref "R41") (pin "P$1") (pinfunction "P$1_P$1") (pintype "passive"))
      (node (ref "U25") (pin "P$1") (pinfunction "ANODE_P$1") (pintype "bidirectional"))
    )
    (net (code "116") (name "Net-(U26-ANODE)") (class "Default")
      (node (ref "R42") (pin "P$1") (pinfunction "P$1_P$1") (pintype "passive"))
      (node (ref "U26") (pin "P$1") (pinfunction "ANODE_P$1") (pintype "bidirectional"))
    )
    (net (code "117") (name "Net-(U27-BYP)") (class "Default")
      (node (ref "C26") (pin "1") (pinfunction "1_1") (pintype "passive"))
      (node (ref "U27") (pin "P$2") (pinfunction "BYP_P$2") (pintype "bidirectional"))
    )
    (net (code "118") (name "Net-(U27-CRST)") (class "Default")
      (node (ref "C40") (pin "1") (pinfunction "1_1") (pintype "passive"))
      (node (ref "U27") (pin "P$8") (pinfunction "CRST_P$8") (pintype "bidirectional"))
    )
    (net (code "119") (name "Net-(U28-VDD1)") (class "Default")
      (node (ref "C45") (pin "1") (pinfunction "1_1") (pintype "passive"))
      (node (ref "U28") (pin "P$1") (pinfunction "VDD1_P$1") (pintype "bidirectional"))
      (node (ref "U30") (pin "P$5") (pinfunction "VOUT_P$5") (pintype "bidirectional"))
    )
    (net (code "120") (name "Net-(U28-VIN)") (class "Default")
      (node (ref "R44") (pin "P$2") (pinfunction "P$2_P$2") (pintype "passive"))
      (node (ref "R45") (pin "P$2") (pinfunction "P$2_P$2") (pintype "passive"))
      (node (ref "U28") (pin "P$2") (pinfunction "VIN_P$2") (pintype "bidirectional"))
    )
    (net (code "121") (name "Net-(U28-VOUT+)") (class "Default")
      (node (ref "C42") (pin "1") (pinfunction "1_1") (pintype "passive"))
      (node (ref "R43") (pin "P$1") (pinfunction "P$1_P$1") (pintype "passive"))
      (node (ref "U28") (pin "P$7") (pinfunction "VOUT+_P$7") (pintype "bidirectional"))
    )
    (net (code "122") (name "unconnected-(J5-PIN2-PadP$2)") (class "Default")
      (node (ref "J5") (pin "P$2") (pinfunction "PIN2_P$2") (pintype "bidirectional"))
    )
    (net (code "123") (name "unconnected-(PROP_TC-PIN1-PadP$1)") (class "Default")
      (node (ref "PROP_TC") (pin "P$1") (pinfunction "PIN1_P$1") (pintype "bidirectional"))
    )
    (net (code "124") (name "unconnected-(PROP_TC-PIN2-PadP$2)") (class "Default")
      (node (ref "PROP_TC") (pin "P$2") (pinfunction "PIN2_P$2") (pintype "bidirectional"))
    )
    (net (code "125") (name "unconnected-(PROP_UART-Pad2)") (class "Default")
      (node (ref "PROP_UART") (pin "2") (pinfunction "2_2") (pintype "passive"))
    )
    (net (code "126") (name "unconnected-(PROP_UART-Pad3)") (class "Default")
      (node (ref "PROP_UART") (pin "3") (pinfunction "3_3") (pintype "passive"))
    )
    (net (code "127") (name "unconnected-(RELAYS-9-PadP$9)") (class "Default")
      (node (ref "RELAYS") (pin "P$9") (pinfunction "9_P$9") (pintype "bidirectional"))
    )
    (net (code "128") (name "unconnected-(RELAYS-10-PadP$10)") (class "Default")
      (node (ref "RELAYS") (pin "P$10") (pinfunction "10_P$10") (pintype "bidirectional"))
    )
    (net (code "129") (name "unconnected-(SW1-PadP$2)") (class "Default")
      (node (ref "SW1") (pin "P$2") (pinfunction "P$2_P$2") (pintype "bidirectional"))
    )
    (net (code "130") (name "unconnected-(SW1-PadP$3)") (class "Default")
      (node (ref "SW1") (pin "P$3") (pinfunction "P$3_P$3") (pintype "bidirectional"))
    )
    (net (code "131") (name "unconnected-(SW2-PadP$2)") (class "Default")
      (node (ref "SW2") (pin "P$2") (pinfunction "P$2_P$2") (pintype "bidirectional"))
    )
    (net (code "132") (name "unconnected-(SW2-PadP$3)") (class "Default")
      (node (ref "SW2") (pin "P$3") (pinfunction "P$3_P$3") (pintype "bidirectional"))
    )
    (net (code "133") (name "unconnected-(SW3-PadP$2)") (class "Default")
      (node (ref "SW3") (pin "P$2") (pinfunction "P$2_P$2") (pintype "bidirectional"))
    )
    (net (code "134") (name "unconnected-(SW3-PadP$3)") (class "Default")
      (node (ref "SW3") (pin "P$3") (pinfunction "P$3_P$3") (pintype "bidirectional"))
    )
    (net (code "135") (name "unconnected-(SWITCHS-9-PadP$9)") (class "Default")
      (node (ref "SWITCHS") (pin "P$9") (pinfunction "9_P$9") (pintype "bidirectional"))
    )
    (net (code "136") (name "unconnected-(SWITCHS-10-PadP$10)") (class "Default")
      (node (ref "SWITCHS") (pin "P$10") (pinfunction "10_P$10") (pintype "bidirectional"))
    )
    (net (code "137") (name "unconnected-(U7-A0-Pad1)") (class "Default")
      (node (ref "U7") (pin "1") (pinfunction "A0_1") (pintype "bidirectional"))
    )
    (net (code "138") (name "unconnected-(U14-Q7S-Pad9)") (class "Default")
      (node (ref "U14") (pin "9") (pinfunction "Q7S_9") (pintype "bidirectional"))
    )
    (net (code "139") (name "unconnected-(U16-QH'-Pad7)") (class "Default")
      (node (ref "U16") (pin "7") (pinfunction "QH'_7") (pintype "bidirectional"))
    )
    (net (code "140") (name "unconnected-(U16-SER-Pad10)") (class "Default")
      (node (ref "U16") (pin "10") (pinfunction "SER_10") (pintype "bidirectional"))
    )
    (net (code "141") (name "unconnected-(U27-INT1-PadP$11)") (class "Default")
      (node (ref "U27") (pin "P$11") (pinfunction "INT1_P$11") (pintype "bidirectional"))
    )
    (net (code "142") (name "unconnected-(U27-INT2-PadP$9)") (class "Default")
      (node (ref "U27") (pin "P$9") (pinfunction "INT2_P$9") (pintype "bidirectional"))
    )
  )
)
